# EIT_sample_circuit_with_shorter_connecto.net
KiCad netlist of a schematic drawn in EAGLE
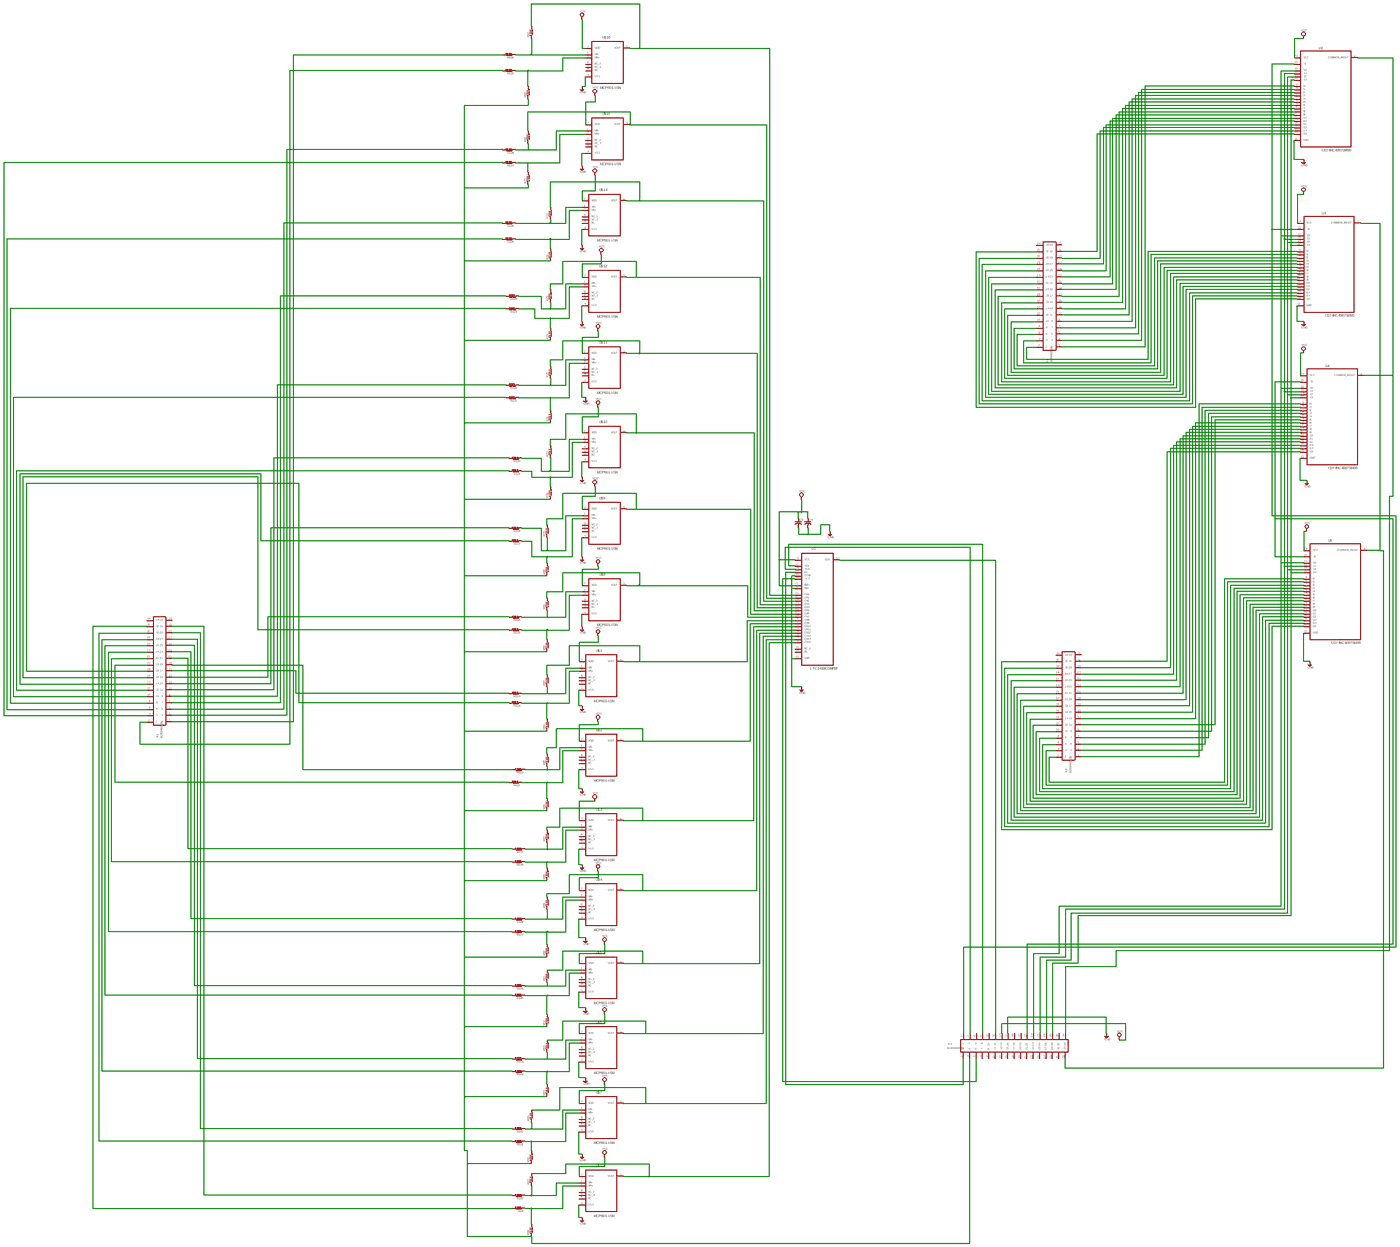
[diagram p0: schematic, sheet 1, overview]
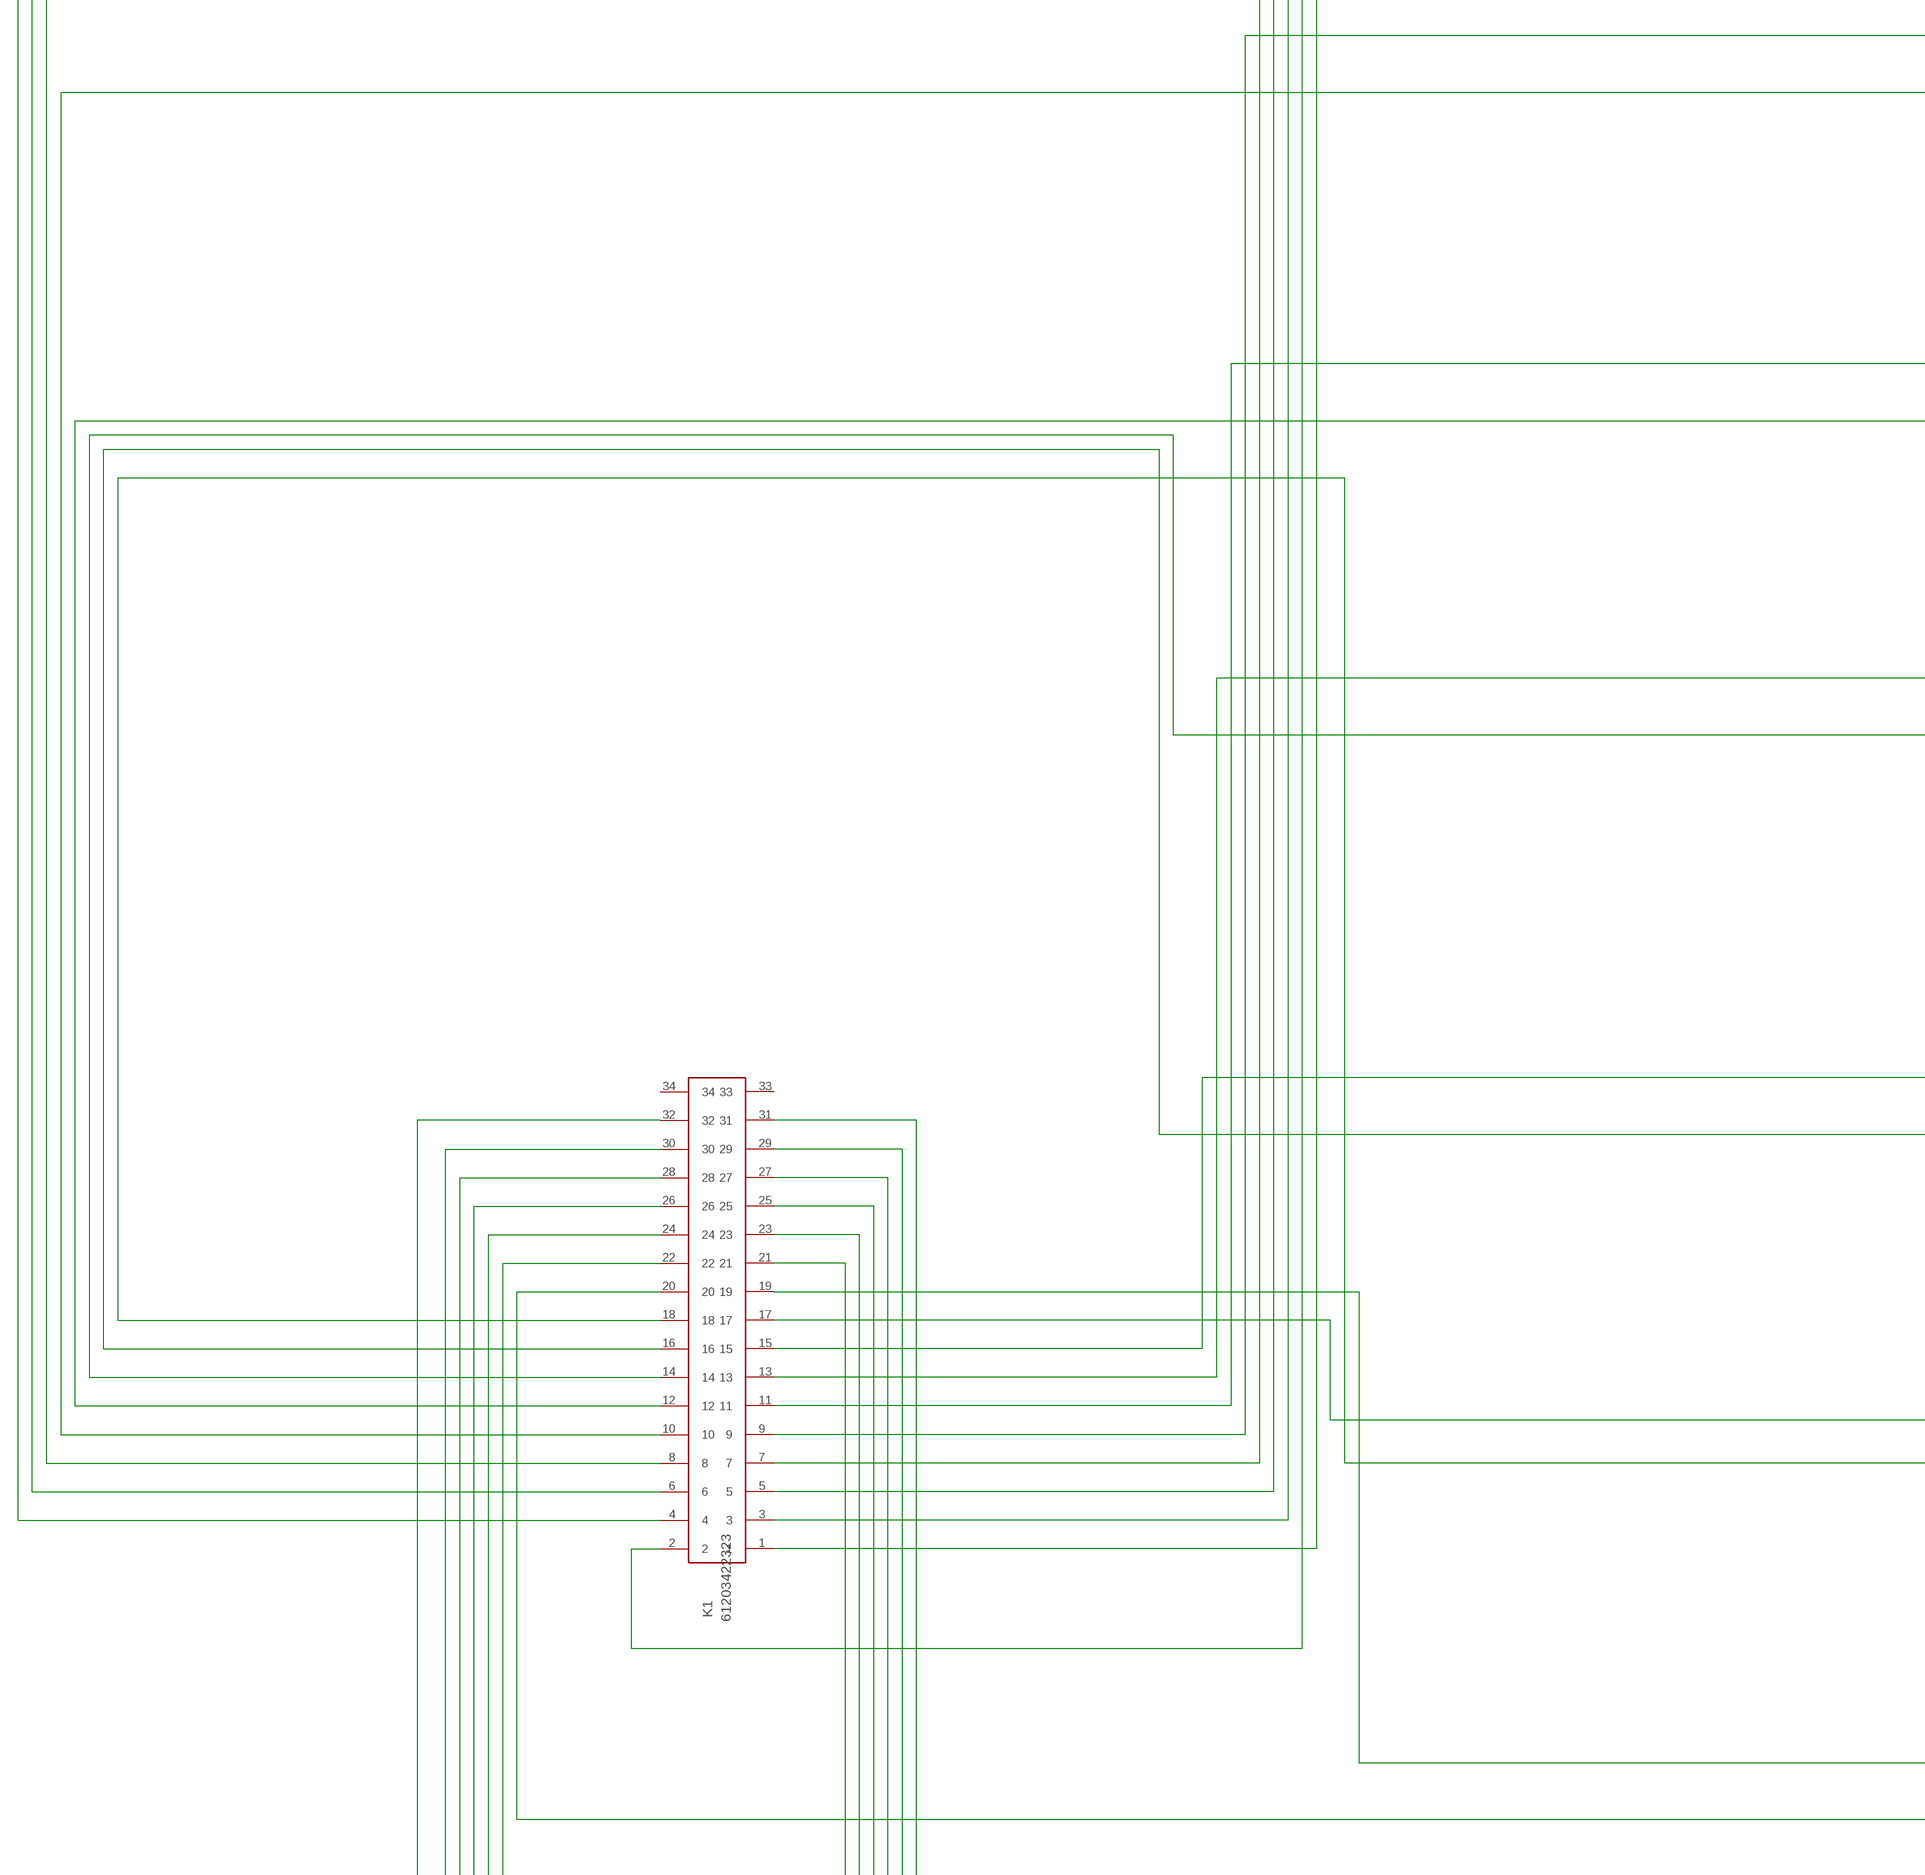
[diagram p1: schematic, sheet 1, part 1 of 7]
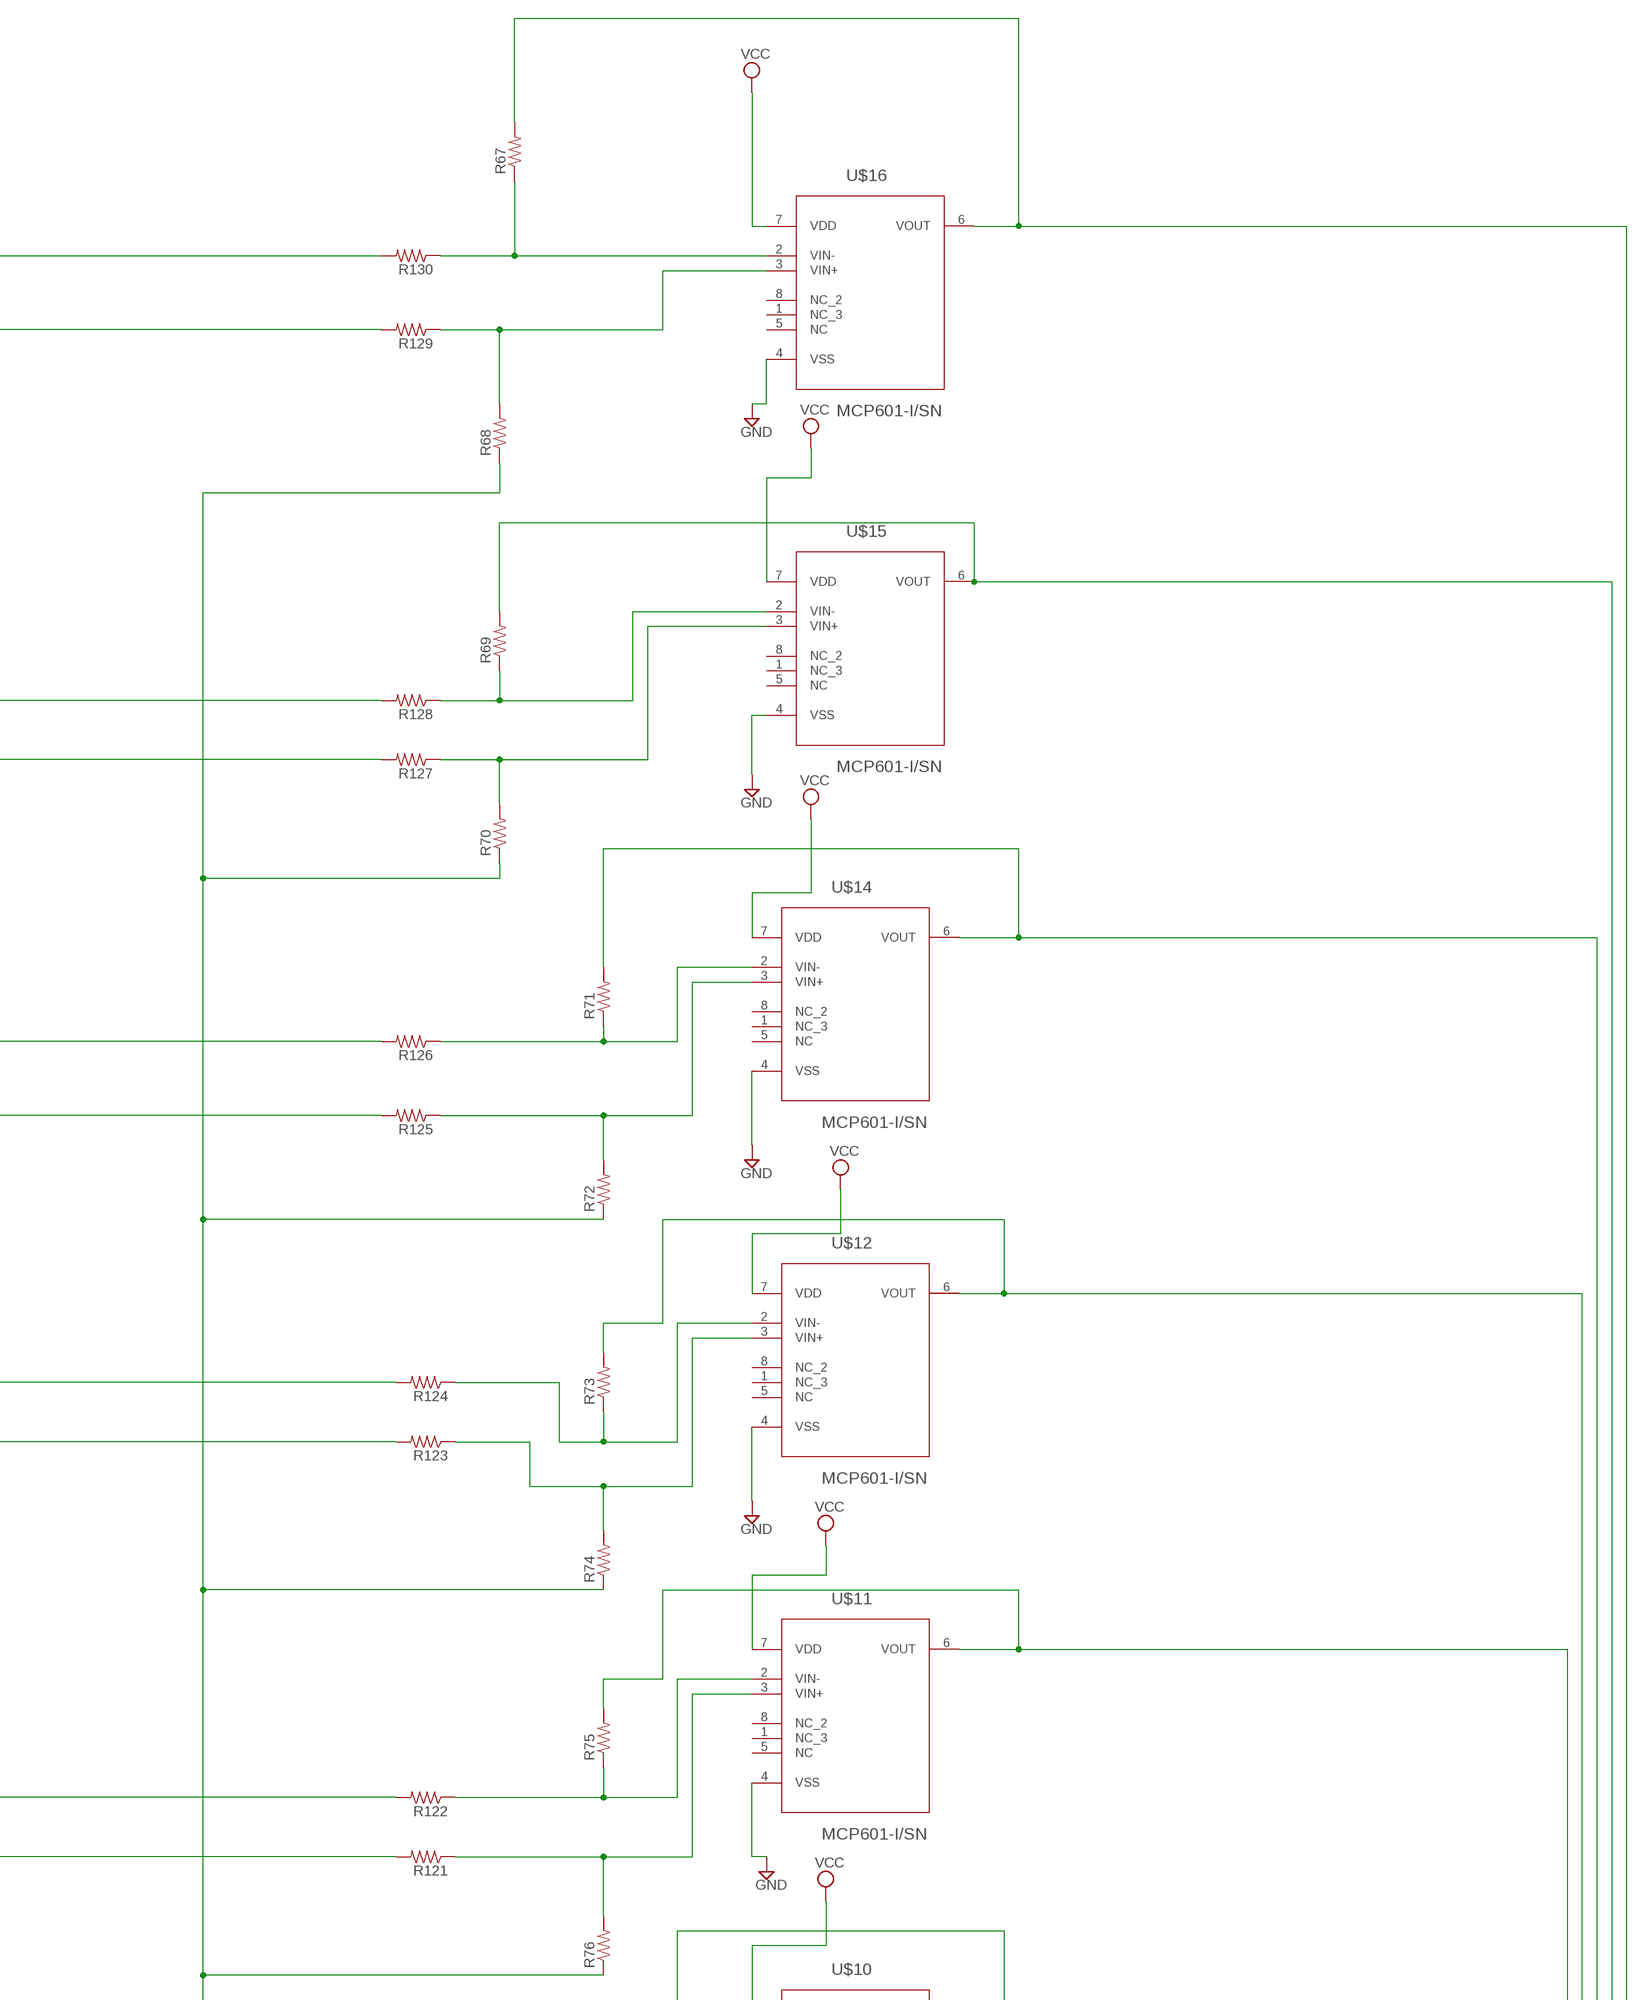
[diagram p2: schematic, sheet 1, part 2 of 7]
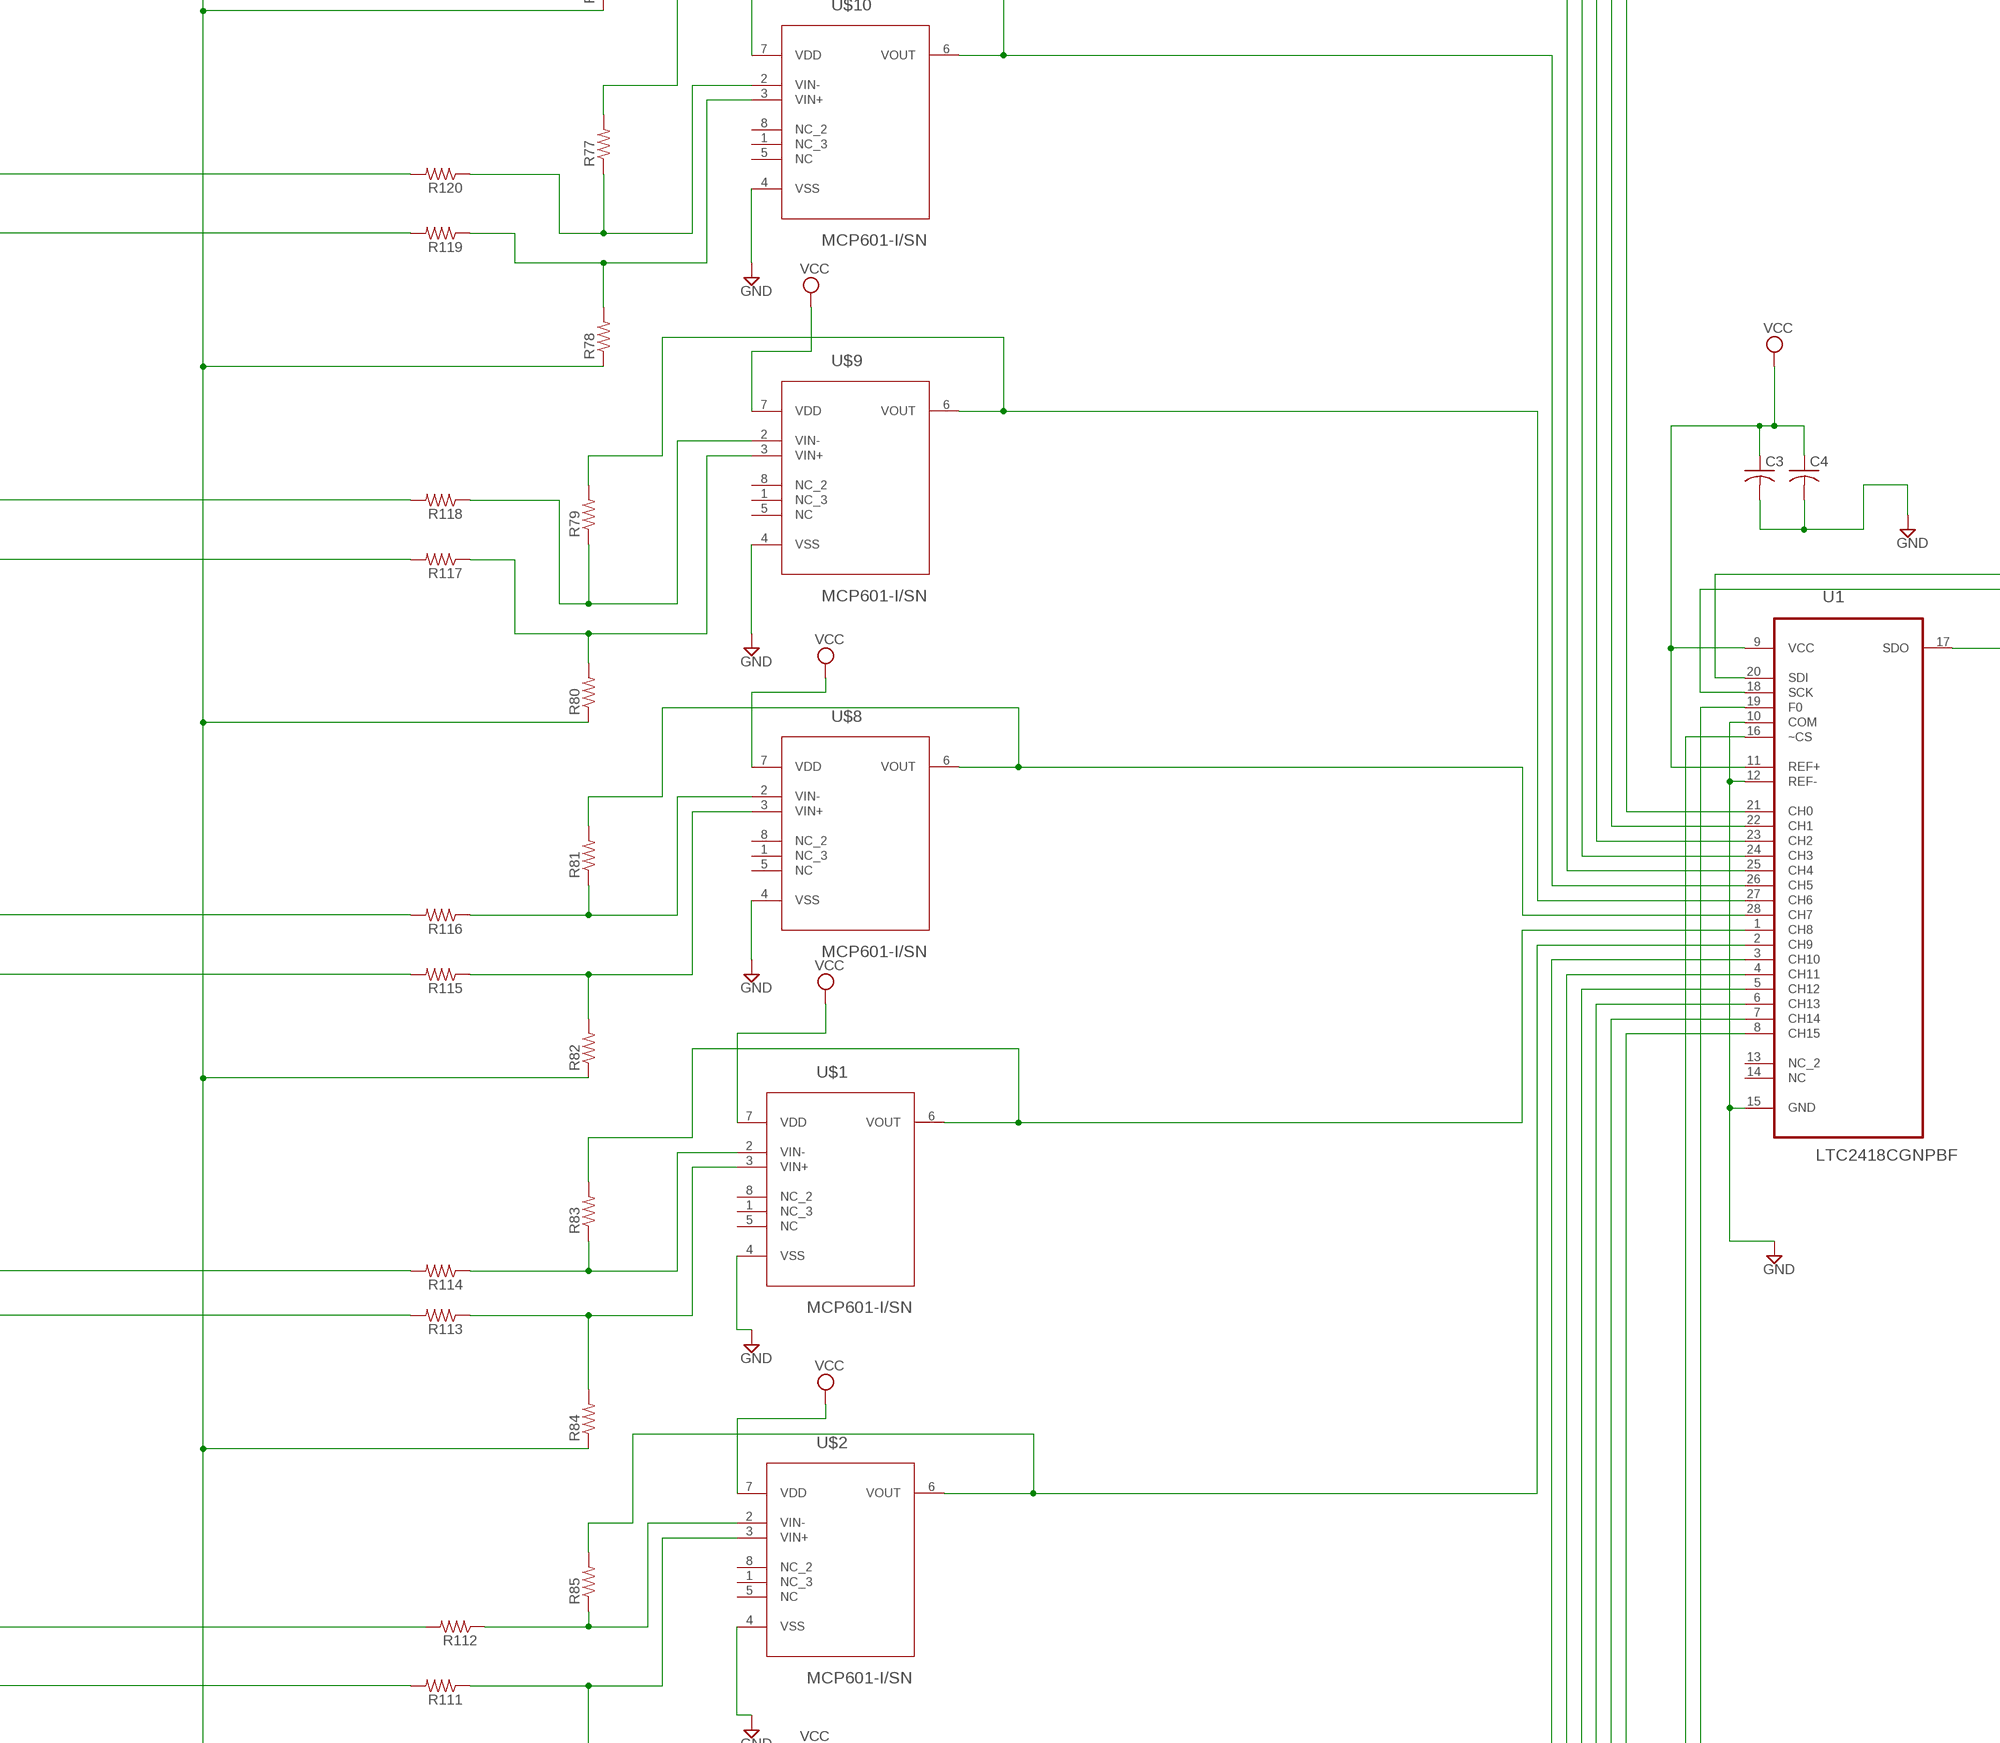
[diagram p3: schematic, sheet 1, part 3 of 7]
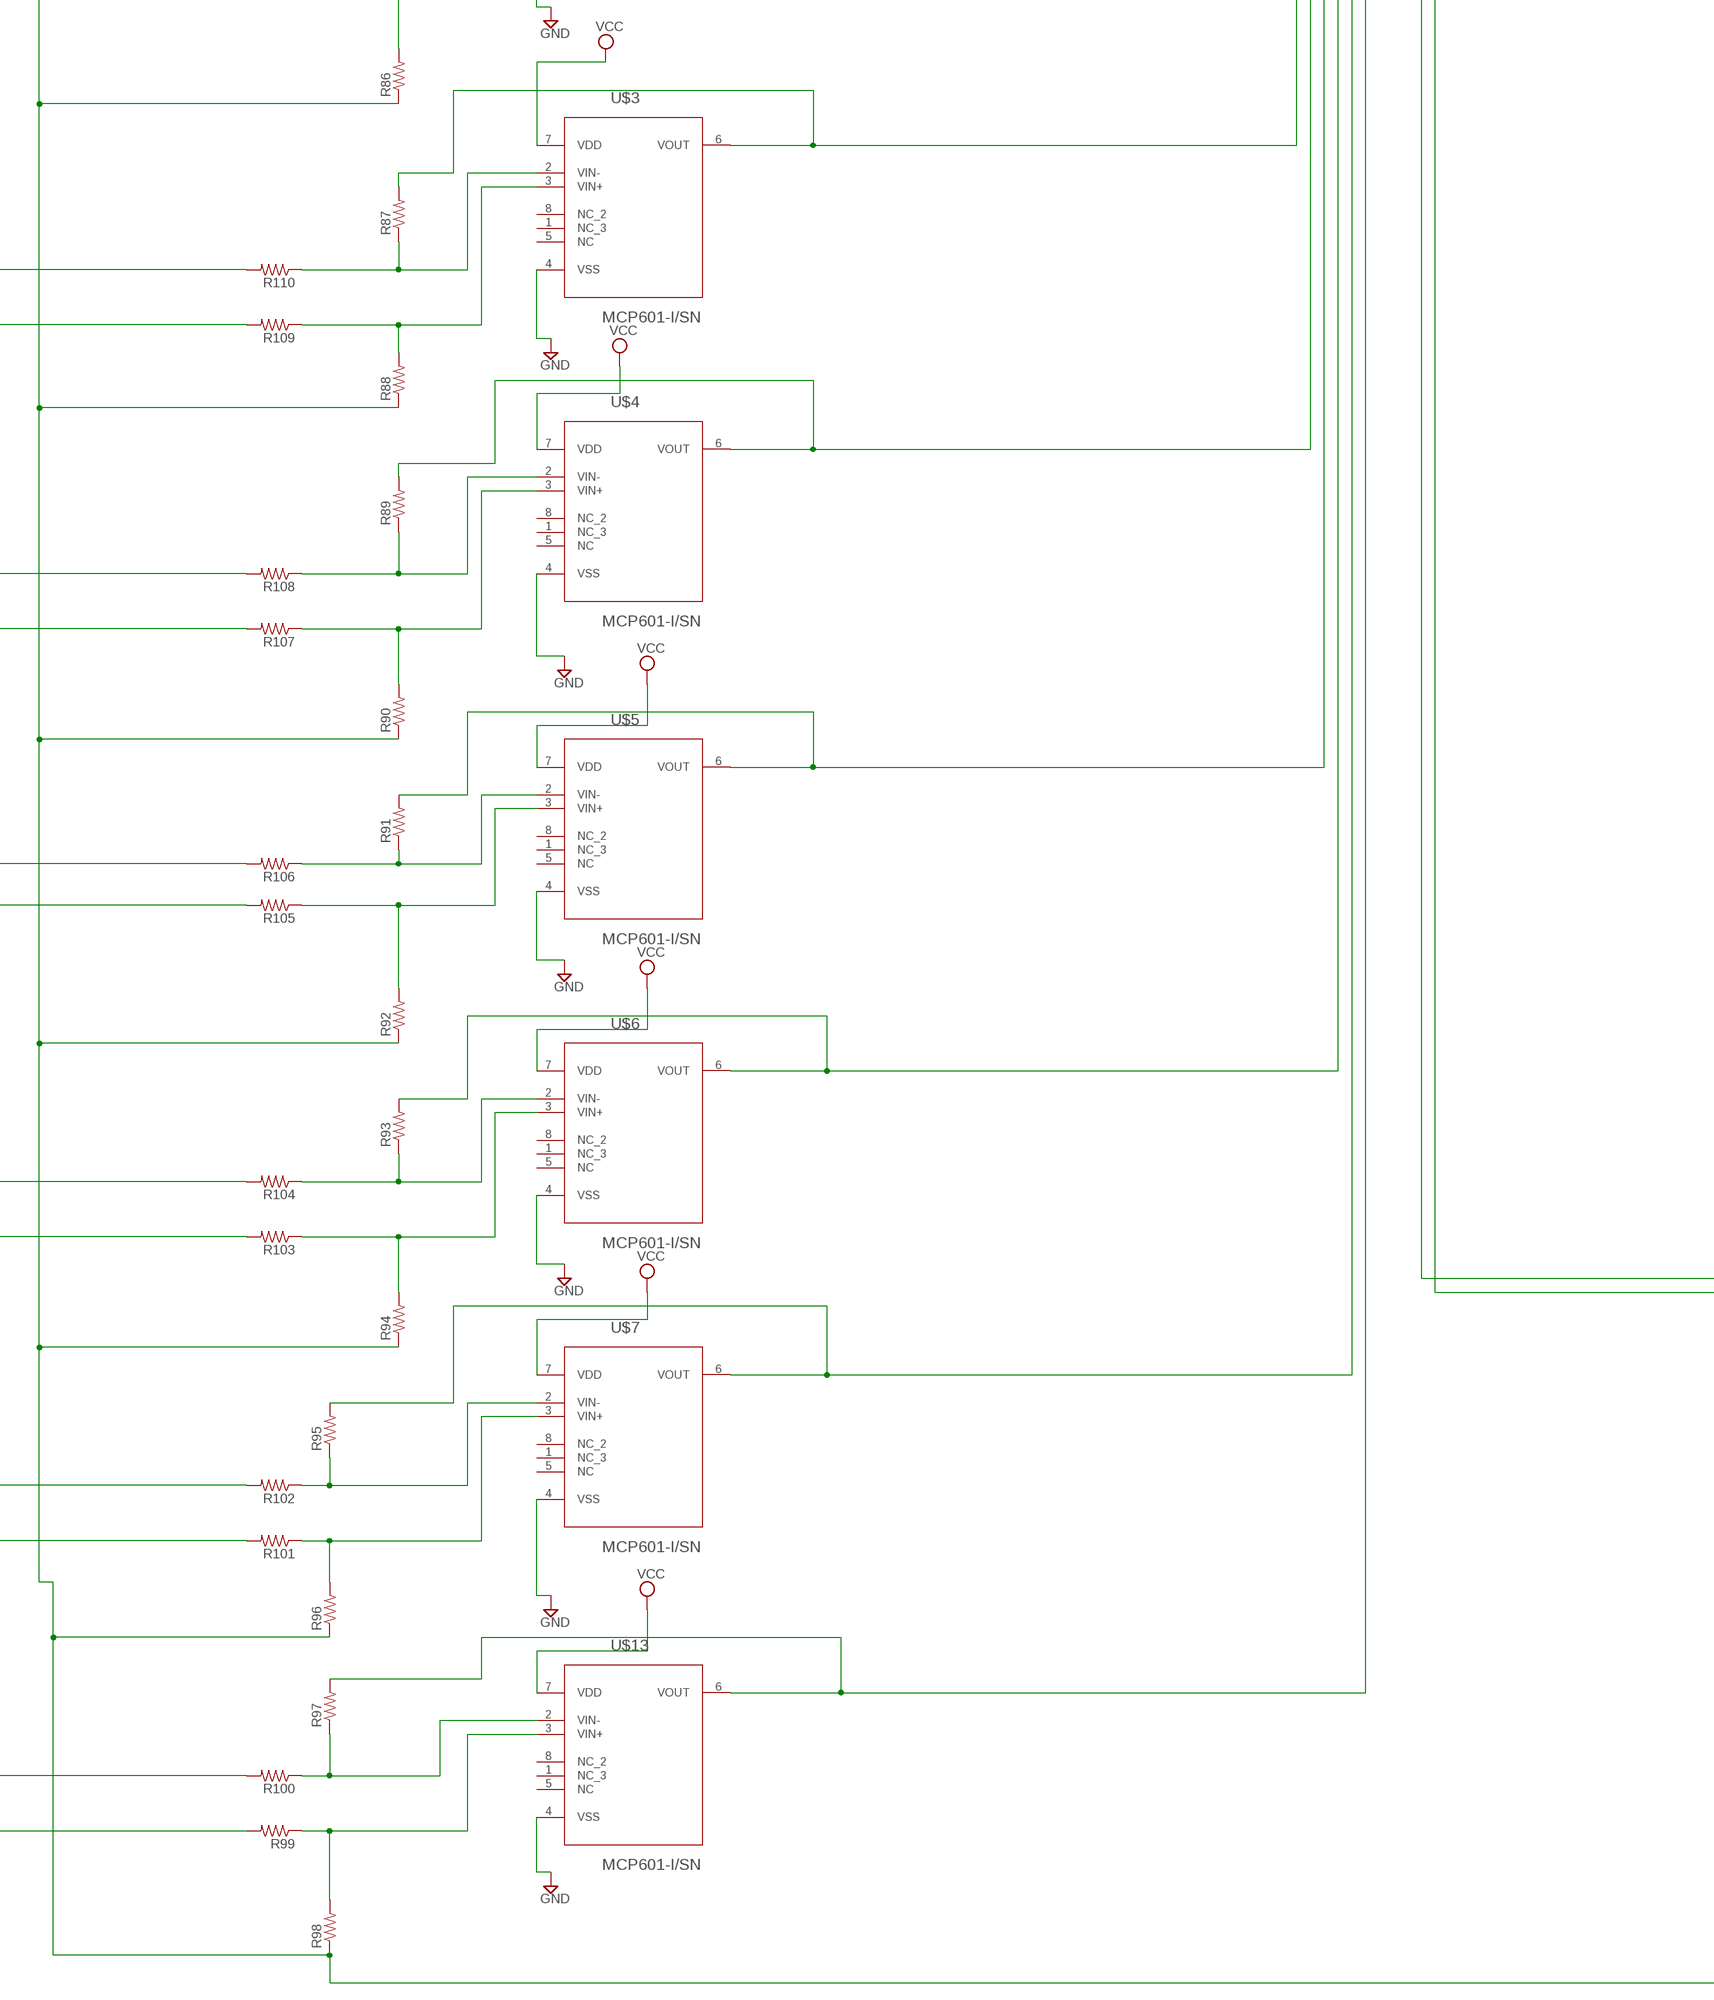
[diagram p4: schematic, sheet 1, part 4 of 7]
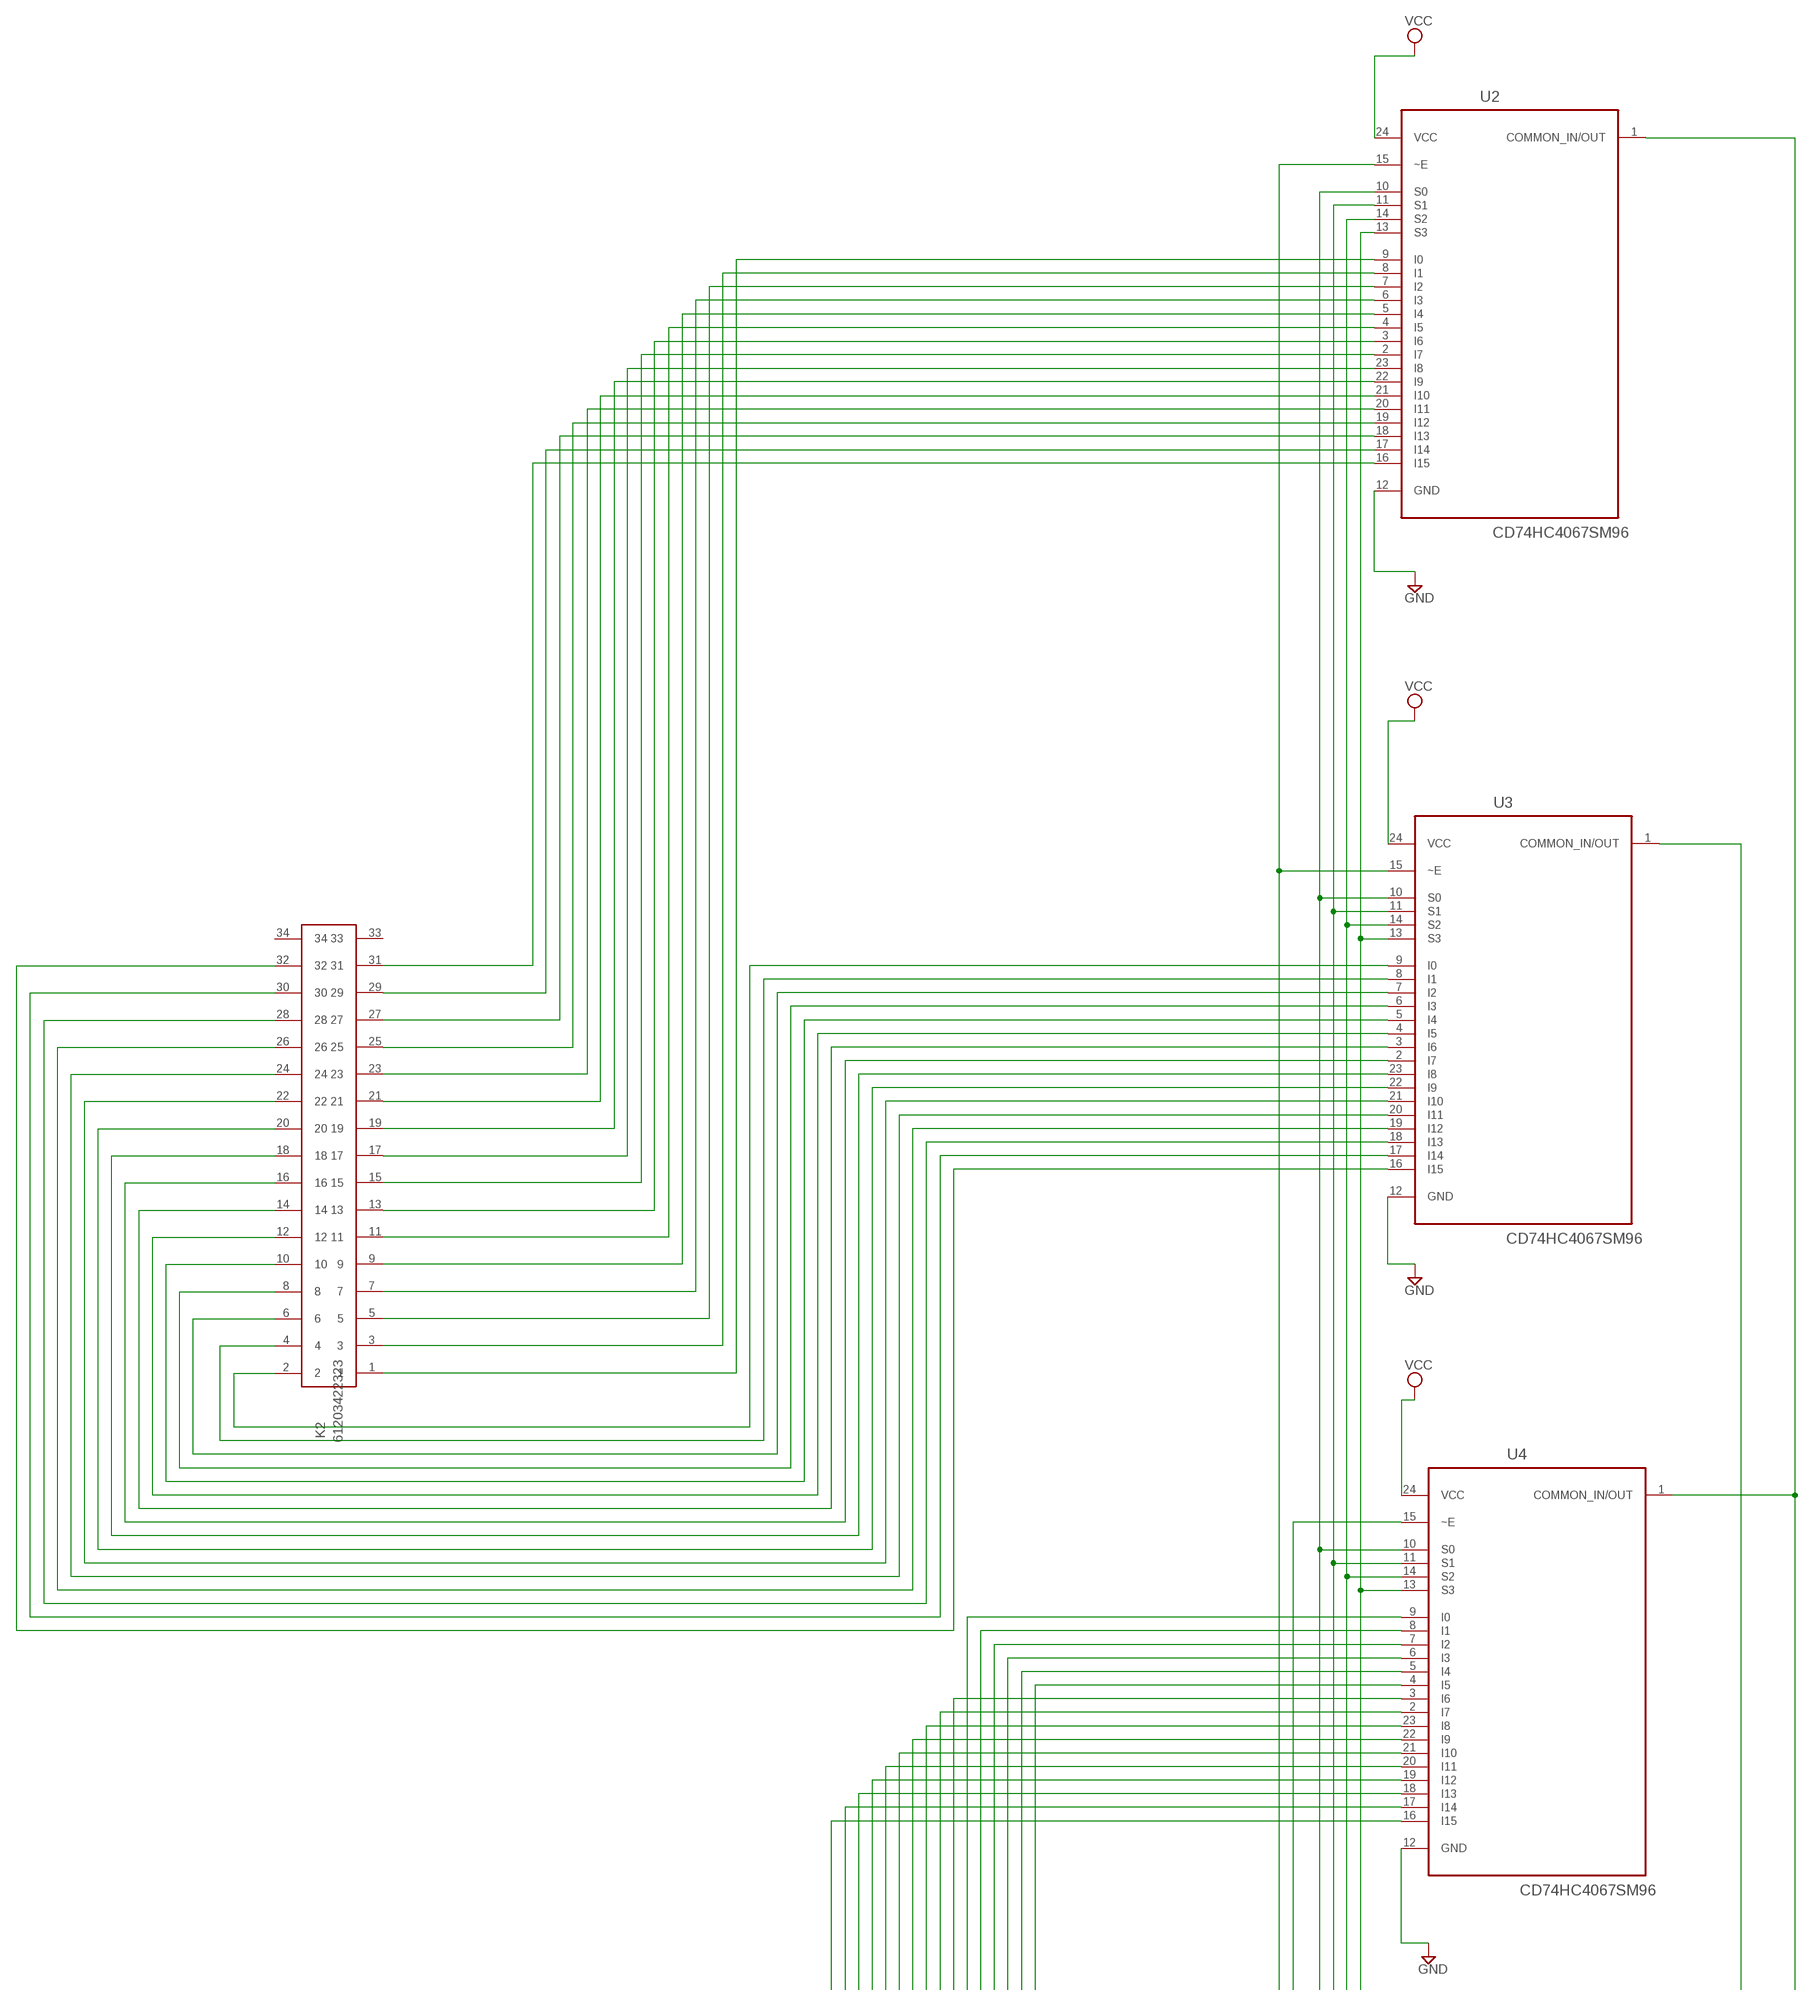
[diagram p5: schematic, sheet 1, part 5 of 7]
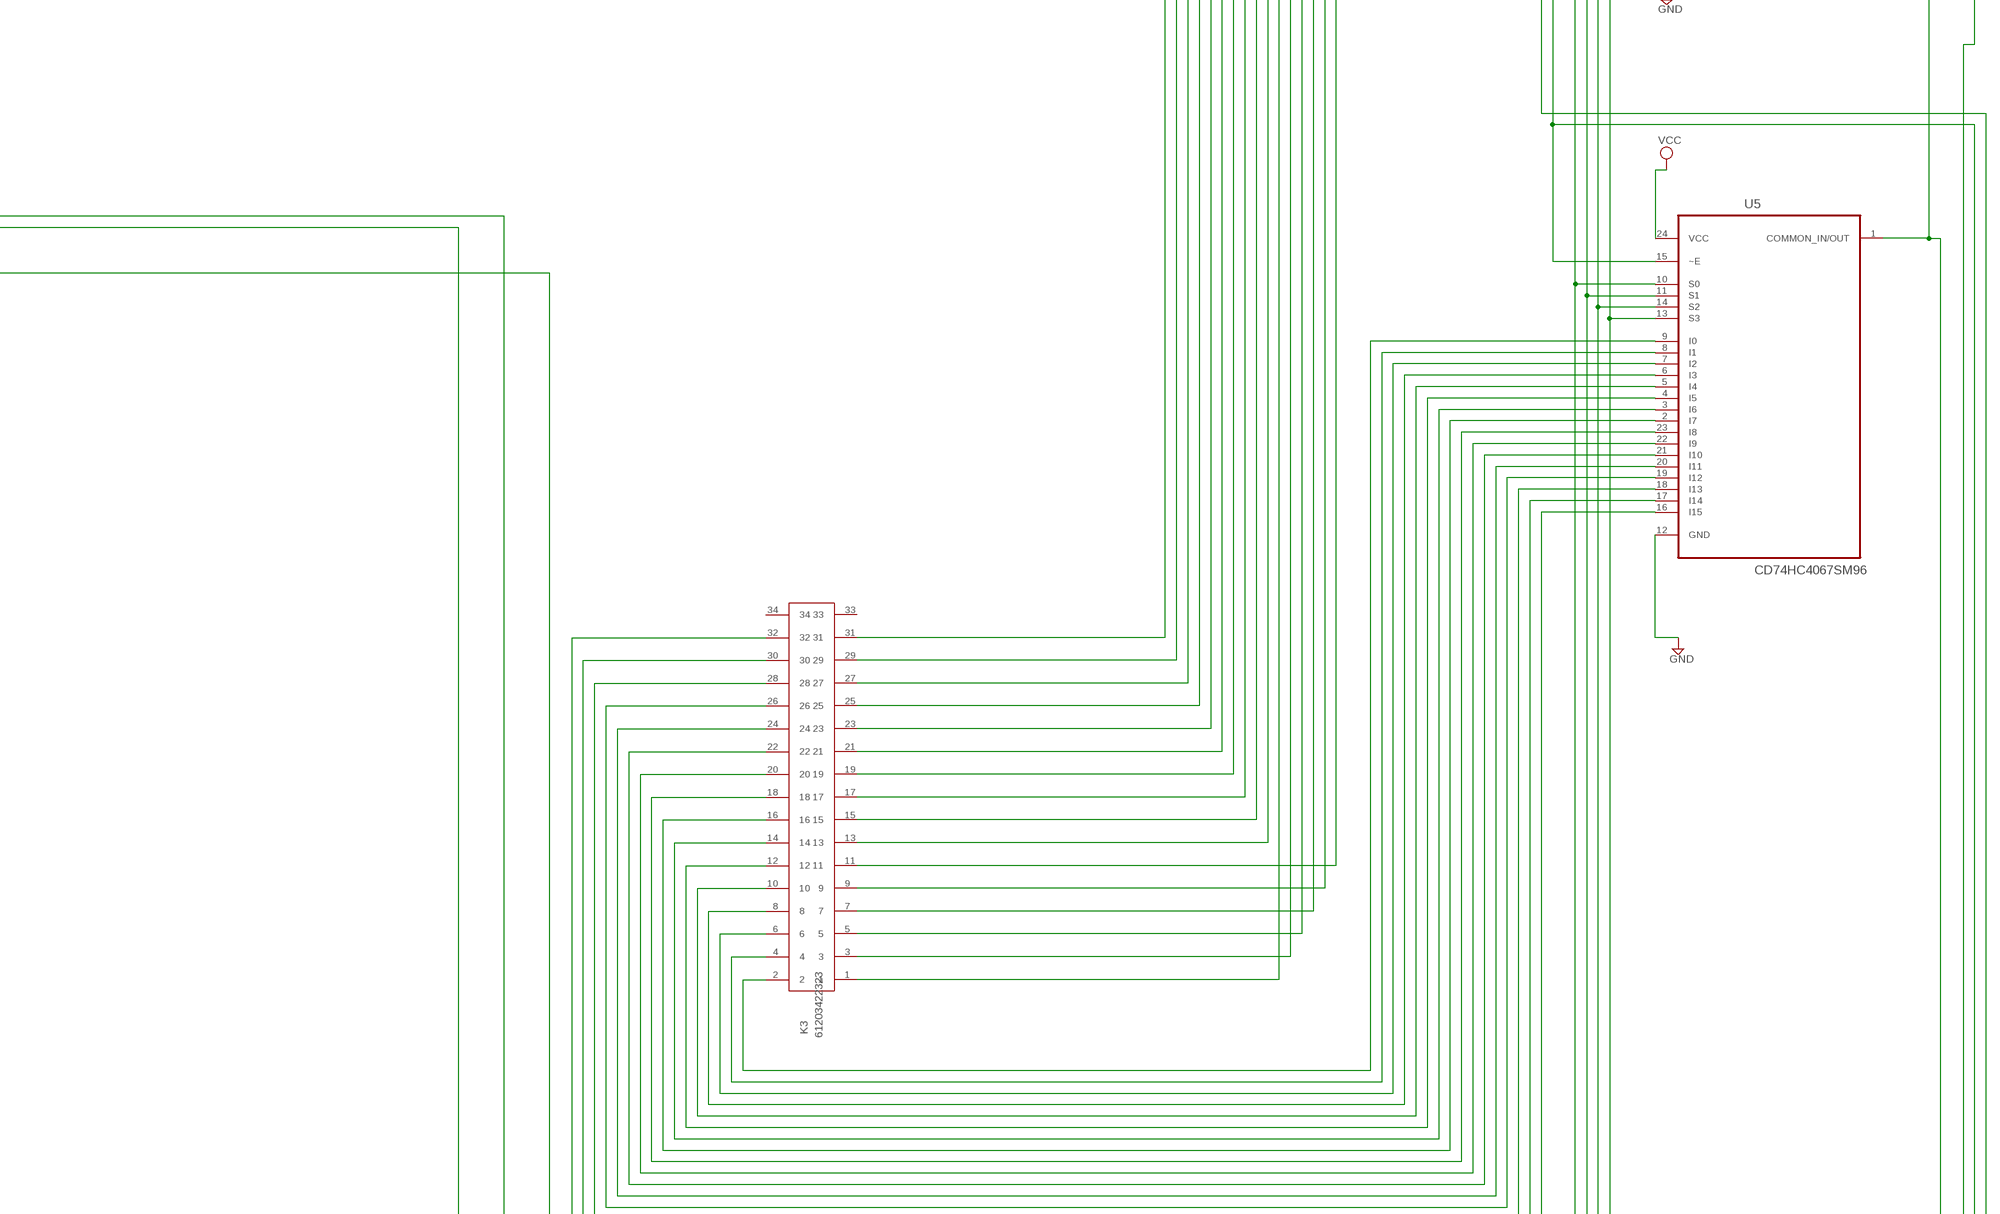
[diagram p6: schematic, sheet 1, part 6 of 7]
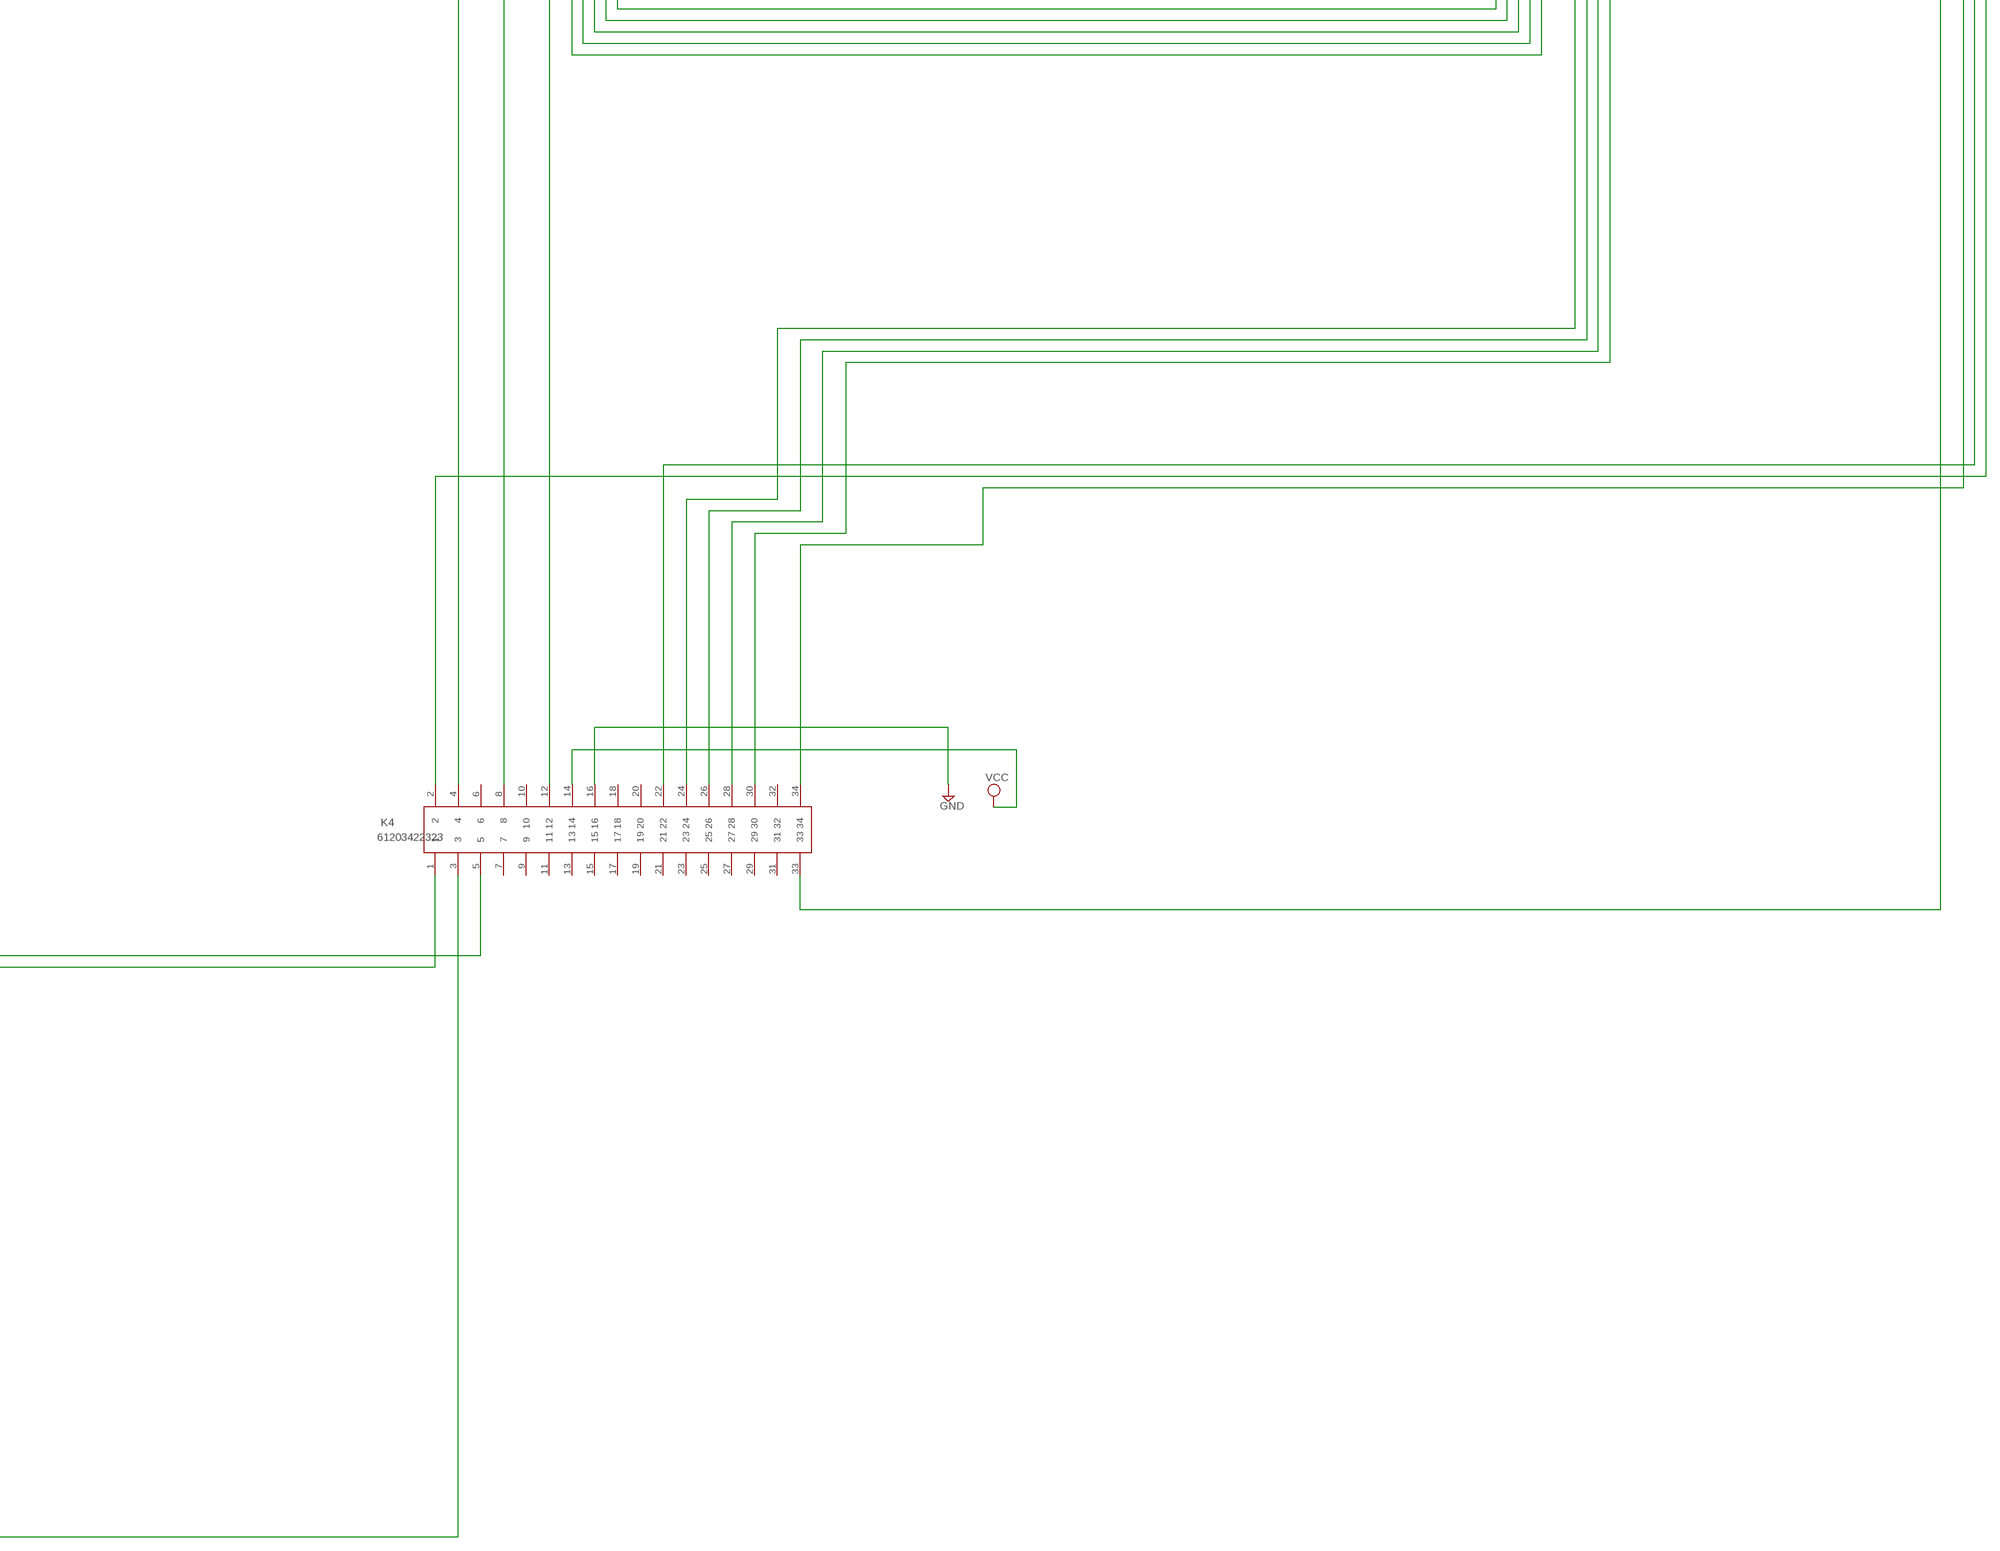
[diagram p7: schematic, sheet 1, part 7 of 7]

(export (version "E")
  (design (tool "Eeschema 10.0.6"))
  (components
    (comp (ref "C3")
      (value "C-US050-030X075")
      (footprint "eagle-import:C050-030X075")
      (libsource (lib "eagle-import") (part "C-US050-030X075"))
    )
    (comp (ref "C4")
      (value "C-US050-030X075")
      (footprint "eagle-import:C050-030X075")
      (libsource (lib "eagle-import") (part "C-US050-030X075"))
    )
    (comp (ref "K1")
      (value "61203422323")
      (footprint "eagle-import:61203422323")
      (libsource (lib "eagle-import") (part "61203422323"))
    )
    (comp (ref "K2")
      (value "61203422323")
      (footprint "eagle-import:61203422323")
      (libsource (lib "eagle-import") (part "61203422323"))
    )
    (comp (ref "K3")
      (value "61203422323")
      (footprint "eagle-import:61203422323")
      (libsource (lib "eagle-import") (part "61203422323"))
    )
    (comp (ref "K4")
      (value "61203422323")
      (footprint "eagle-import:61203422323")
      (libsource (lib "eagle-import") (part "61203422323"))
    )
    (comp (ref "R67")
      (value "R-US_0207/10")
      (footprint "eagle-import:0207_10")
      (libsource (lib "eagle-import") (part "R-US_0207/10"))
    )
    (comp (ref "R68")
      (value "R-US_0207/10")
      (footprint "eagle-import:0207_10")
      (libsource (lib "eagle-import") (part "R-US_0207/10"))
    )
    (comp (ref "R69")
      (value "R-US_0207/10")
      (footprint "eagle-import:0207_10")
      (libsource (lib "eagle-import") (part "R-US_0207/10"))
    )
    (comp (ref "R70")
      (value "R-US_0207/10")
      (footprint "eagle-import:0207_10")
      (libsource (lib "eagle-import") (part "R-US_0207/10"))
    )
    (comp (ref "R71")
      (value "R-US_0207/10")
      (footprint "eagle-import:0207_10")
      (libsource (lib "eagle-import") (part "R-US_0207/10"))
    )
    (comp (ref "R72")
      (value "R-US_0207/10")
      (footprint "eagle-import:0207_10")
      (libsource (lib "eagle-import") (part "R-US_0207/10"))
    )
    (comp (ref "R73")
      (value "R-US_0207/10")
      (footprint "eagle-import:0207_10")
      (libsource (lib "eagle-import") (part "R-US_0207/10"))
    )
    (comp (ref "R74")
      (value "R-US_0207/10")
      (footprint "eagle-import:0207_10")
      (libsource (lib "eagle-import") (part "R-US_0207/10"))
    )
    (comp (ref "R75")
      (value "R-US_0207/10")
      (footprint "eagle-import:0207_10")
      (libsource (lib "eagle-import") (part "R-US_0207/10"))
    )
    (comp (ref "R76")
      (value "R-US_0207/10")
      (footprint "eagle-import:0207_10")
      (libsource (lib "eagle-import") (part "R-US_0207/10"))
    )
    (comp (ref "R77")
      (value "R-US_0207/10")
      (footprint "eagle-import:0207_10")
      (libsource (lib "eagle-import") (part "R-US_0207/10"))
    )
    (comp (ref "R78")
      (value "R-US_0207/10")
      (footprint "eagle-import:0207_10")
      (libsource (lib "eagle-import") (part "R-US_0207/10"))
    )
    (comp (ref "R79")
      (value "R-US_0207/10")
      (footprint "eagle-import:0207_10")
      (libsource (lib "eagle-import") (part "R-US_0207/10"))
    )
    (comp (ref "R80")
      (value "R-US_0207/10")
      (footprint "eagle-import:0207_10")
      (libsource (lib "eagle-import") (part "R-US_0207/10"))
    )
    (comp (ref "R81")
      (value "R-US_0207/10")
      (footprint "eagle-import:0207_10")
      (libsource (lib "eagle-import") (part "R-US_0207/10"))
    )
    (comp (ref "R82")
      (value "R-US_0207/10")
      (footprint "eagle-import:0207_10")
      (libsource (lib "eagle-import") (part "R-US_0207/10"))
    )
    (comp (ref "R83")
      (value "R-US_0207/10")
      (footprint "eagle-import:0207_10")
      (libsource (lib "eagle-import") (part "R-US_0207/10"))
    )
    (comp (ref "R84")
      (value "R-US_0207/10")
      (footprint "eagle-import:0207_10")
      (libsource (lib "eagle-import") (part "R-US_0207/10"))
    )
    (comp (ref "R85")
      (value "R-US_0207/10")
      (footprint "eagle-import:0207_10")
      (libsource (lib "eagle-import") (part "R-US_0207/10"))
    )
    (comp (ref "R86")
      (value "R-US_0207/10")
      (footprint "eagle-import:0207_10")
      (libsource (lib "eagle-import") (part "R-US_0207/10"))
    )
    (comp (ref "R87")
      (value "R-US_0207/10")
      (footprint "eagle-import:0207_10")
      (libsource (lib "eagle-import") (part "R-US_0207/10"))
    )
    (comp (ref "R88")
      (value "R-US_0207/10")
      (footprint "eagle-import:0207_10")
      (libsource (lib "eagle-import") (part "R-US_0207/10"))
    )
    (comp (ref "R89")
      (value "R-US_0207/10")
      (footprint "eagle-import:0207_10")
      (libsource (lib "eagle-import") (part "R-US_0207/10"))
    )
    (comp (ref "R90")
      (value "R-US_0207/10")
      (footprint "eagle-import:0207_10")
      (libsource (lib "eagle-import") (part "R-US_0207/10"))
    )
    (comp (ref "R91")
      (value "R-US_0207/10")
      (footprint "eagle-import:0207_10")
      (libsource (lib "eagle-import") (part "R-US_0207/10"))
    )
    (comp (ref "R92")
      (value "R-US_0207/10")
      (footprint "eagle-import:0207_10")
      (libsource (lib "eagle-import") (part "R-US_0207/10"))
    )
    (comp (ref "R93")
      (value "R-US_0207/10")
      (footprint "eagle-import:0207_10")
      (libsource (lib "eagle-import") (part "R-US_0207/10"))
    )
    (comp (ref "R94")
      (value "R-US_0207/10")
      (footprint "eagle-import:0207_10")
      (libsource (lib "eagle-import") (part "R-US_0207/10"))
    )
    (comp (ref "R95")
      (value "R-US_0207/10")
      (footprint "eagle-import:0207_10")
      (libsource (lib "eagle-import") (part "R-US_0207/10"))
    )
    (comp (ref "R96")
      (value "R-US_0207/10")
      (footprint "eagle-import:0207_10")
      (libsource (lib "eagle-import") (part "R-US_0207/10"))
    )
    (comp (ref "R97")
      (value "R-US_0207/10")
      (footprint "eagle-import:0207_10")
      (libsource (lib "eagle-import") (part "R-US_0207/10"))
    )
    (comp (ref "R98")
      (value "R-US_0207/10")
      (footprint "eagle-import:0207_10")
      (libsource (lib "eagle-import") (part "R-US_0207/10"))
    )
    (comp (ref "R99")
      (value "R-US_0207/7")
      (footprint "eagle-import:0207_7")
      (libsource (lib "eagle-import") (part "R-US_0207/7"))
    )
    (comp (ref "R100")
      (value "R-US_0207/7")
      (footprint "eagle-import:0207_7")
      (libsource (lib "eagle-import") (part "R-US_0207/7"))
    )
    (comp (ref "R101")
      (value "R-US_0207/7")
      (footprint "eagle-import:0207_7")
      (libsource (lib "eagle-import") (part "R-US_0207/7"))
    )
    (comp (ref "R102")
      (value "R-US_0207/7")
      (footprint "eagle-import:0207_7")
      (libsource (lib "eagle-import") (part "R-US_0207/7"))
    )
    (comp (ref "R103")
      (value "R-US_0207/7")
      (footprint "eagle-import:0207_7")
      (libsource (lib "eagle-import") (part "R-US_0207/7"))
    )
    (comp (ref "R104")
      (value "R-US_0207/7")
      (footprint "eagle-import:0207_7")
      (libsource (lib "eagle-import") (part "R-US_0207/7"))
    )
    (comp (ref "R105")
      (value "R-US_0207/7")
      (footprint "eagle-import:0207_7")
      (libsource (lib "eagle-import") (part "R-US_0207/7"))
    )
    (comp (ref "R106")
      (value "R-US_0207/7")
      (footprint "eagle-import:0207_7")
      (libsource (lib "eagle-import") (part "R-US_0207/7"))
    )
    (comp (ref "R107")
      (value "R-US_0207/7")
      (footprint "eagle-import:0207_7")
      (libsource (lib "eagle-import") (part "R-US_0207/7"))
    )
    (comp (ref "R108")
      (value "R-US_0207/7")
      (footprint "eagle-import:0207_7")
      (libsource (lib "eagle-import") (part "R-US_0207/7"))
    )
    (comp (ref "R109")
      (value "R-US_0207/7")
      (footprint "eagle-import:0207_7")
      (libsource (lib "eagle-import") (part "R-US_0207/7"))
    )
    (comp (ref "R110")
      (value "R-US_0207/7")
      (footprint "eagle-import:0207_7")
      (libsource (lib "eagle-import") (part "R-US_0207/7"))
    )
    (comp (ref "R111")
      (value "R-US_0207/7")
      (footprint "eagle-import:0207_7")
      (libsource (lib "eagle-import") (part "R-US_0207/7"))
    )
    (comp (ref "R112")
      (value "R-US_0207/7")
      (footprint "eagle-import:0207_7")
      (libsource (lib "eagle-import") (part "R-US_0207/7"))
    )
    (comp (ref "R113")
      (value "R-US_0207/7")
      (footprint "eagle-import:0207_7")
      (libsource (lib "eagle-import") (part "R-US_0207/7"))
    )
    (comp (ref "R114")
      (value "R-US_0207/7")
      (footprint "eagle-import:0207_7")
      (libsource (lib "eagle-import") (part "R-US_0207/7"))
    )
    (comp (ref "R115")
      (value "R-US_0207/7")
      (footprint "eagle-import:0207_7")
      (libsource (lib "eagle-import") (part "R-US_0207/7"))
    )
    (comp (ref "R116")
      (value "R-US_0207/7")
      (footprint "eagle-import:0207_7")
      (libsource (lib "eagle-import") (part "R-US_0207/7"))
    )
    (comp (ref "R117")
      (value "R-US_0207/7")
      (footprint "eagle-import:0207_7")
      (libsource (lib "eagle-import") (part "R-US_0207/7"))
    )
    (comp (ref "R118")
      (value "R-US_0207/7")
      (footprint "eagle-import:0207_7")
      (libsource (lib "eagle-import") (part "R-US_0207/7"))
    )
    (comp (ref "R119")
      (value "R-US_0207/7")
      (footprint "eagle-import:0207_7")
      (libsource (lib "eagle-import") (part "R-US_0207/7"))
    )
    (comp (ref "R120")
      (value "R-US_0207/7")
      (footprint "eagle-import:0207_7")
      (libsource (lib "eagle-import") (part "R-US_0207/7"))
    )
    (comp (ref "R121")
      (value "R-US_0207/7")
      (footprint "eagle-import:0207_7")
      (libsource (lib "eagle-import") (part "R-US_0207/7"))
    )
    (comp (ref "R122")
      (value "R-US_0207/7")
      (footprint "eagle-import:0207_7")
      (libsource (lib "eagle-import") (part "R-US_0207/7"))
    )
    (comp (ref "R123")
      (value "R-US_0207/7")
      (footprint "eagle-import:0207_7")
      (libsource (lib "eagle-import") (part "R-US_0207/7"))
    )
    (comp (ref "R124")
      (value "R-US_0207/7")
      (footprint "eagle-import:0207_7")
      (libsource (lib "eagle-import") (part "R-US_0207/7"))
    )
    (comp (ref "R125")
      (value "R-US_0207/7")
      (footprint "eagle-import:0207_7")
      (libsource (lib "eagle-import") (part "R-US_0207/7"))
    )
    (comp (ref "R126")
      (value "R-US_0207/7")
      (footprint "eagle-import:0207_7")
      (libsource (lib "eagle-import") (part "R-US_0207/7"))
    )
    (comp (ref "R127")
      (value "R-US_0207/7")
      (footprint "eagle-import:0207_7")
      (libsource (lib "eagle-import") (part "R-US_0207/7"))
    )
    (comp (ref "R128")
      (value "R-US_0207/7")
      (footprint "eagle-import:0207_7")
      (libsource (lib "eagle-import") (part "R-US_0207/7"))
    )
    (comp (ref "R129")
      (value "R-US_0207/7")
      (footprint "eagle-import:0207_7")
      (libsource (lib "eagle-import") (part "R-US_0207/7"))
    )
    (comp (ref "R130")
      (value "R-US_0207/7")
      (footprint "eagle-import:0207_7")
      (libsource (lib "eagle-import") (part "R-US_0207/7"))
    )
    (comp (ref "U$1")
      (value "MCP601-I/SN")
      (footprint "eagle-import:SOIC127P600X175-8N")
      (libsource (lib "eagle-import") (part "MCP601-I/SN"))
    )
    (comp (ref "U$2")
      (value "MCP601-I/SN")
      (footprint "eagle-import:SOIC127P600X175-8N")
      (libsource (lib "eagle-import") (part "MCP601-I/SN"))
    )
    (comp (ref "U$3")
      (value "MCP601-I/SN")
      (footprint "eagle-import:SOIC127P600X175-8N")
      (libsource (lib "eagle-import") (part "MCP601-I/SN"))
    )
    (comp (ref "U$4")
      (value "MCP601-I/SN")
      (footprint "eagle-import:SOIC127P600X175-8N")
      (libsource (lib "eagle-import") (part "MCP601-I/SN"))
    )
    (comp (ref "U$5")
      (value "MCP601-I/SN")
      (footprint "eagle-import:SOIC127P600X175-8N")
      (libsource (lib "eagle-import") (part "MCP601-I/SN"))
    )
    (comp (ref "U$6")
      (value "MCP601-I/SN")
      (footprint "eagle-import:SOIC127P600X175-8N")
      (libsource (lib "eagle-import") (part "MCP601-I/SN"))
    )
    (comp (ref "U$7")
      (value "MCP601-I/SN")
      (footprint "eagle-import:SOIC127P600X175-8N")
      (libsource (lib "eagle-import") (part "MCP601-I/SN"))
    )
    (comp (ref "U$8")
      (value "MCP601-I/SN")
      (footprint "eagle-import:SOIC127P600X175-8N")
      (libsource (lib "eagle-import") (part "MCP601-I/SN"))
    )
    (comp (ref "U$9")
      (value "MCP601-I/SN")
      (footprint "eagle-import:SOIC127P600X175-8N")
      (libsource (lib "eagle-import") (part "MCP601-I/SN"))
    )
    (comp (ref "U$10")
      (value "MCP601-I/SN")
      (footprint "eagle-import:SOIC127P600X175-8N")
      (libsource (lib "eagle-import") (part "MCP601-I/SN"))
    )
    (comp (ref "U$11")
      (value "MCP601-I/SN")
      (footprint "eagle-import:SOIC127P600X175-8N")
      (libsource (lib "eagle-import") (part "MCP601-I/SN"))
    )
    (comp (ref "U$12")
      (value "MCP601-I/SN")
      (footprint "eagle-import:SOIC127P600X175-8N")
      (libsource (lib "eagle-import") (part "MCP601-I/SN"))
    )
    (comp (ref "U$13")
      (value "MCP601-I/SN")
      (footprint "eagle-import:SOIC127P600X175-8N")
      (libsource (lib "eagle-import") (part "MCP601-I/SN"))
    )
    (comp (ref "U$14")
      (value "MCP601-I/SN")
      (footprint "eagle-import:SOIC127P600X175-8N")
      (libsource (lib "eagle-import") (part "MCP601-I/SN"))
    )
    (comp (ref "U$15")
      (value "MCP601-I/SN")
      (footprint "eagle-import:SOIC127P600X175-8N")
      (libsource (lib "eagle-import") (part "MCP601-I/SN"))
    )
    (comp (ref "U$16")
      (value "MCP601-I/SN")
      (footprint "eagle-import:SOIC127P600X175-8N")
      (libsource (lib "eagle-import") (part "MCP601-I/SN"))
    )
    (comp (ref "U1")
      (value "LTC2418CGNPBF")
      (footprint "eagle-import:SOP63P600X175-28N")
      (fields (field (name "MPN") "LTC2418CGN#PBF"))
      (libsource (lib "eagle-import") (part "LTC2418CGNPBF"))
    )
    (comp (ref "U2")
      (value "CD74HC4067SM96")
      (footprint "eagle-import:SOP65P780X200-24N")
      (libsource (lib "eagle-import") (part "CD74HC4067SM96"))
    )
    (comp (ref "U3")
      (value "CD74HC4067SM96")
      (footprint "eagle-import:SOP65P780X200-24N")
      (libsource (lib "eagle-import") (part "CD74HC4067SM96"))
    )
    (comp (ref "U4")
      (value "CD74HC4067SM96")
      (footprint "eagle-import:SOP65P780X200-24N")
      (libsource (lib "eagle-import") (part "CD74HC4067SM96"))
    )
    (comp (ref "U5")
      (value "CD74HC4067SM96")
      (footprint "eagle-import:SOP65P780X200-24N")
      (libsource (lib "eagle-import") (part "CD74HC4067SM96"))
    )
  )
  (nets
    (net (code "1") (name "GND") (class "Default")
      (node (ref "C3") (pin "2") (pinfunction "2_2") (pintype "passive"))
      (node (ref "C4") (pin "2") (pinfunction "2_2") (pintype "passive"))
      (node (ref "K4") (pin "16") (pinfunction "16_16") (pintype "passive"))
      (node (ref "U$1") (pin "4") (pinfunction "VSS_4") (pintype "power_in"))
      (node (ref "U$10") (pin "4") (pinfunction "VSS_4") (pintype "power_in"))
      (node (ref "U$11") (pin "4") (pinfunction "VSS_4") (pintype "power_in"))
      (node (ref "U$12") (pin "4") (pinfunction "VSS_4") (pintype "power_in"))
      (node (ref "U$13") (pin "4") (pinfunction "VSS_4") (pintype "power_in"))
      (node (ref "U$14") (pin "4") (pinfunction "VSS_4") (pintype "power_in"))
      (node (ref "U$15") (pin "4") (pinfunction "VSS_4") (pintype "power_in"))
      (node (ref "U$16") (pin "4") (pinfunction "VSS_4") (pintype "power_in"))
      (node (ref "U$2") (pin "4") (pinfunction "VSS_4") (pintype "power_in"))
      (node (ref "U$3") (pin "4") (pinfunction "VSS_4") (pintype "power_in"))
      (node (ref "U$4") (pin "4") (pinfunction "VSS_4") (pintype "power_in"))
      (node (ref "U$5") (pin "4") (pinfunction "VSS_4") (pintype "power_in"))
      (node (ref "U$6") (pin "4") (pinfunction "VSS_4") (pintype "power_in"))
      (node (ref "U$7") (pin "4") (pinfunction "VSS_4") (pintype "power_in"))
      (node (ref "U$8") (pin "4") (pinfunction "VSS_4") (pintype "power_in"))
      (node (ref "U$9") (pin "4") (pinfunction "VSS_4") (pintype "power_in"))
      (node (ref "U1") (pin "10") (pinfunction "COM_10") (pintype "input"))
      (node (ref "U1") (pin "12") (pinfunction "REF-_12") (pintype "input"))
      (node (ref "U1") (pin "15") (pinfunction "GND_15") (pintype "passive"))
      (node (ref "U2") (pin "12") (pinfunction "GND_12") (pintype "passive"))
      (node (ref "U3") (pin "12") (pinfunction "GND_12") (pintype "passive"))
      (node (ref "U4") (pin "12") (pinfunction "GND_12") (pintype "passive"))
      (node (ref "U5") (pin "12") (pinfunction "GND_12") (pintype "passive"))
    )
    (net (code "2") (name "Net-(K1-Pad1)") (class "Default")
      (node (ref "K1") (pin "1") (pinfunction "1_1") (pintype "passive"))
      (node (ref "R130") (pin "2") (pinfunction "2_2") (pintype "passive"))
    )
    (net (code "3") (name "Net-(K1-Pad2)") (class "Default")
      (node (ref "K1") (pin "2") (pinfunction "2_2") (pintype "passive"))
      (node (ref "R129") (pin "2") (pinfunction "2_2") (pintype "passive"))
    )
    (net (code "4") (name "Net-(K1-Pad3)") (class "Default")
      (node (ref "K1") (pin "3") (pinfunction "3_3") (pintype "passive"))
      (node (ref "R128") (pin "2") (pinfunction "2_2") (pintype "passive"))
    )
    (net (code "5") (name "Net-(K1-Pad4)") (class "Default")
      (node (ref "K1") (pin "4") (pinfunction "4_4") (pintype "passive"))
      (node (ref "R127") (pin "2") (pinfunction "2_2") (pintype "passive"))
    )
    (net (code "6") (name "Net-(K1-Pad5)") (class "Default")
      (node (ref "K1") (pin "5") (pinfunction "5_5") (pintype "passive"))
      (node (ref "R126") (pin "2") (pinfunction "2_2") (pintype "passive"))
    )
    (net (code "7") (name "Net-(K1-Pad6)") (class "Default")
      (node (ref "K1") (pin "6") (pinfunction "6_6") (pintype "passive"))
      (node (ref "R125") (pin "2") (pinfunction "2_2") (pintype "passive"))
    )
    (net (code "8") (name "Net-(K1-Pad7)") (class "Default")
      (node (ref "K1") (pin "7") (pinfunction "7_7") (pintype "passive"))
      (node (ref "R124") (pin "2") (pinfunction "2_2") (pintype "passive"))
    )
    (net (code "9") (name "Net-(K1-Pad8)") (class "Default")
      (node (ref "K1") (pin "8") (pinfunction "8_8") (pintype "passive"))
      (node (ref "R123") (pin "2") (pinfunction "2_2") (pintype "passive"))
    )
    (net (code "10") (name "Net-(K1-Pad9)") (class "Default")
      (node (ref "K1") (pin "9") (pinfunction "9_9") (pintype "passive"))
      (node (ref "R122") (pin "2") (pinfunction "2_2") (pintype "passive"))
    )
    (net (code "11") (name "Net-(K1-Pad10)") (class "Default")
      (node (ref "K1") (pin "10") (pinfunction "10_10") (pintype "passive"))
      (node (ref "R121") (pin "2") (pinfunction "2_2") (pintype "passive"))
    )
    (net (code "12") (name "Net-(K1-Pad11)") (class "Default")
      (node (ref "K1") (pin "11") (pinfunction "11_11") (pintype "passive"))
      (node (ref "R120") (pin "2") (pinfunction "2_2") (pintype "passive"))
    )
    (net (code "13") (name "Net-(K1-Pad12)") (class "Default")
      (node (ref "K1") (pin "12") (pinfunction "12_12") (pintype "passive"))
      (node (ref "R119") (pin "2") (pinfunction "2_2") (pintype "passive"))
    )
    (net (code "14") (name "Net-(K1-Pad13)") (class "Default")
      (node (ref "K1") (pin "13") (pinfunction "13_13") (pintype "passive"))
      (node (ref "R118") (pin "2") (pinfunction "2_2") (pintype "passive"))
    )
    (net (code "15") (name "Net-(K1-Pad14)") (class "Default")
      (node (ref "K1") (pin "14") (pinfunction "14_14") (pintype "passive"))
      (node (ref "R117") (pin "2") (pinfunction "2_2") (pintype "passive"))
    )
    (net (code "16") (name "Net-(K1-Pad15)") (class "Default")
      (node (ref "K1") (pin "15") (pinfunction "15_15") (pintype "passive"))
      (node (ref "R116") (pin "2") (pinfunction "2_2") (pintype "passive"))
    )
    (net (code "17") (name "Net-(K1-Pad16)") (class "Default")
      (node (ref "K1") (pin "16") (pinfunction "16_16") (pintype "passive"))
      (node (ref "R115") (pin "2") (pinfunction "2_2") (pintype "passive"))
    )
    (net (code "18") (name "Net-(K1-Pad17)") (class "Default")
      (node (ref "K1") (pin "17") (pinfunction "17_17") (pintype "passive"))
      (node (ref "R114") (pin "2") (pinfunction "2_2") (pintype "passive"))
    )
    (net (code "19") (name "Net-(K1-Pad18)") (class "Default")
      (node (ref "K1") (pin "18") (pinfunction "18_18") (pintype "passive"))
      (node (ref "R113") (pin "2") (pinfunction "2_2") (pintype "passive"))
    )
    (net (code "20") (name "Net-(K1-Pad19)") (class "Default")
      (node (ref "K1") (pin "19") (pinfunction "19_19") (pintype "passive"))
      (node (ref "R112") (pin "2") (pinfunction "2_2") (pintype "passive"))
    )
    (net (code "21") (name "Net-(K1-Pad20)") (class "Default")
      (node (ref "K1") (pin "20") (pinfunction "20_20") (pintype "passive"))
      (node (ref "R111") (pin "2") (pinfunction "2_2") (pintype "passive"))
    )
    (net (code "22") (name "Net-(K1-Pad21)") (class "Default")
      (node (ref "K1") (pin "21") (pinfunction "21_21") (pintype "passive"))
      (node (ref "R110") (pin "2") (pinfunction "2_2") (pintype "passive"))
    )
    (net (code "23") (name "Net-(K1-Pad22)") (class "Default")
      (node (ref "K1") (pin "22") (pinfunction "22_22") (pintype "passive"))
      (node (ref "R109") (pin "2") (pinfunction "2_2") (pintype "passive"))
    )
    (net (code "24") (name "Net-(K1-Pad23)") (class "Default")
      (node (ref "K1") (pin "23") (pinfunction "23_23") (pintype "passive"))
      (node (ref "R108") (pin "2") (pinfunction "2_2") (pintype "passive"))
    )
    (net (code "25") (name "Net-(K1-Pad24)") (class "Default")
      (node (ref "K1") (pin "24") (pinfunction "24_24") (pintype "passive"))
      (node (ref "R107") (pin "2") (pinfunction "2_2") (pintype "passive"))
    )
    (net (code "26") (name "Net-(K1-Pad25)") (class "Default")
      (node (ref "K1") (pin "25") (pinfunction "25_25") (pintype "passive"))
      (node (ref "R106") (pin "2") (pinfunction "2_2") (pintype "passive"))
    )
    (net (code "27") (name "Net-(K1-Pad26)") (class "Default")
      (node (ref "K1") (pin "26") (pinfunction "26_26") (pintype "passive"))
      (node (ref "R105") (pin "2") (pinfunction "2_2") (pintype "passive"))
    )
    (net (code "28") (name "Net-(K1-Pad27)") (class "Default")
      (node (ref "K1") (pin "27") (pinfunction "27_27") (pintype "passive"))
      (node (ref "R104") (pin "2") (pinfunction "2_2") (pintype "passive"))
    )
    (net (code "29") (name "Net-(K1-Pad28)") (class "Default")
      (node (ref "K1") (pin "28") (pinfunction "28_28") (pintype "passive"))
      (node (ref "R103") (pin "2") (pinfunction "2_2") (pintype "passive"))
    )
    (net (code "30") (name "Net-(K1-Pad29)") (class "Default")
      (node (ref "K1") (pin "29") (pinfunction "29_29") (pintype "passive"))
      (node (ref "R102") (pin "2") (pinfunction "2_2") (pintype "passive"))
    )
    (net (code "31") (name "Net-(K1-Pad30)") (class "Default")
      (node (ref "K1") (pin "30") (pinfunction "30_30") (pintype "passive"))
      (node (ref "R101") (pin "2") (pinfunction "2_2") (pintype "passive"))
    )
    (net (code "32") (name "Net-(K1-Pad31)") (class "Default")
      (node (ref "K1") (pin "31") (pinfunction "31_31") (pintype "passive"))
      (node (ref "R100") (pin "2") (pinfunction "2_2") (pintype "passive"))
    )
    (net (code "33") (name "Net-(K1-Pad32)") (class "Default")
      (node (ref "K1") (pin "32") (pinfunction "32_32") (pintype "passive"))
      (node (ref "R99") (pin "2") (pinfunction "2_2") (pintype "passive"))
    )
    (net (code "34") (name "Net-(K4-Pad3)") (class "Default")
      (node (ref "K4") (pin "3") (pinfunction "3_3") (pintype "passive"))
      (node (ref "R68") (pin "1") (pinfunction "1_1") (pintype "passive"))
      (node (ref "R70") (pin "1") (pinfunction "1_1") (pintype "passive"))
      (node (ref "R72") (pin "1") (pinfunction "1_1") (pintype "passive"))
      (node (ref "R74") (pin "1") (pinfunction "1_1") (pintype "passive"))
      (node (ref "R76") (pin "1") (pinfunction "1_1") (pintype "passive"))
      (node (ref "R78") (pin "1") (pinfunction "1_1") (pintype "passive"))
      (node (ref "R80") (pin "1") (pinfunction "1_1") (pintype "passive"))
      (node (ref "R82") (pin "1") (pinfunction "1_1") (pintype "passive"))
      (node (ref "R84") (pin "1") (pinfunction "1_1") (pintype "passive"))
      (node (ref "R86") (pin "1") (pinfunction "1_1") (pintype "passive"))
      (node (ref "R88") (pin "1") (pinfunction "1_1") (pintype "passive"))
      (node (ref "R90") (pin "1") (pinfunction "1_1") (pintype "passive"))
      (node (ref "R92") (pin "1") (pinfunction "1_1") (pintype "passive"))
      (node (ref "R94") (pin "1") (pinfunction "1_1") (pintype "passive"))
      (node (ref "R96") (pin "1") (pinfunction "1_1") (pintype "passive"))
      (node (ref "R98") (pin "1") (pinfunction "1_1") (pintype "passive"))
    )
    (net (code "35") (name "Net-(U$1-VIN+)") (class "Default")
      (node (ref "R113") (pin "1") (pinfunction "1_1") (pintype "passive"))
      (node (ref "R84") (pin "2") (pinfunction "2_2") (pintype "passive"))
      (node (ref "U$1") (pin "3") (pinfunction "VIN+_3") (pintype "input"))
    )
    (net (code "36") (name "Net-(U$1-VIN-)") (class "Default")
      (node (ref "R114") (pin "1") (pinfunction "1_1") (pintype "passive"))
      (node (ref "R83") (pin "1") (pinfunction "1_1") (pintype "passive"))
      (node (ref "U$1") (pin "2") (pinfunction "VIN-_2") (pintype "input"))
    )
    (net (code "37") (name "Net-(U$1-VOUT)") (class "Default")
      (node (ref "R83") (pin "2") (pinfunction "2_2") (pintype "passive"))
      (node (ref "U$1") (pin "6") (pinfunction "VOUT_6") (pintype "output"))
      (node (ref "U1") (pin "1") (pinfunction "CH8_1") (pintype "input"))
    )
    (net (code "38") (name "Net-(U$2-VIN+)") (class "Default")
      (node (ref "R111") (pin "1") (pinfunction "1_1") (pintype "passive"))
      (node (ref "R86") (pin "2") (pinfunction "2_2") (pintype "passive"))
      (node (ref "U$2") (pin "3") (pinfunction "VIN+_3") (pintype "input"))
    )
    (net (code "39") (name "Net-(U$2-VIN-)") (class "Default")
      (node (ref "R112") (pin "1") (pinfunction "1_1") (pintype "passive"))
      (node (ref "R85") (pin "1") (pinfunction "1_1") (pintype "passive"))
      (node (ref "U$2") (pin "2") (pinfunction "VIN-_2") (pintype "input"))
    )
    (net (code "40") (name "Net-(U$2-VOUT)") (class "Default")
      (node (ref "R85") (pin "2") (pinfunction "2_2") (pintype "passive"))
      (node (ref "U$2") (pin "6") (pinfunction "VOUT_6") (pintype "output"))
      (node (ref "U1") (pin "2") (pinfunction "CH9_2") (pintype "input"))
    )
    (net (code "41") (name "Net-(U$3-VIN+)") (class "Default")
      (node (ref "R109") (pin "1") (pinfunction "1_1") (pintype "passive"))
      (node (ref "R88") (pin "2") (pinfunction "2_2") (pintype "passive"))
      (node (ref "U$3") (pin "3") (pinfunction "VIN+_3") (pintype "input"))
    )
    (net (code "42") (name "Net-(U$3-VIN-)") (class "Default")
      (node (ref "R110") (pin "1") (pinfunction "1_1") (pintype "passive"))
      (node (ref "R87") (pin "1") (pinfunction "1_1") (pintype "passive"))
      (node (ref "U$3") (pin "2") (pinfunction "VIN-_2") (pintype "input"))
    )
    (net (code "43") (name "Net-(U$3-VOUT)") (class "Default")
      (node (ref "R87") (pin "2") (pinfunction "2_2") (pintype "passive"))
      (node (ref "U$3") (pin "6") (pinfunction "VOUT_6") (pintype "output"))
      (node (ref "U1") (pin "3") (pinfunction "CH10_3") (pintype "input"))
    )
    (net (code "44") (name "Net-(U$4-VIN+)") (class "Default")
      (node (ref "R107") (pin "1") (pinfunction "1_1") (pintype "passive"))
      (node (ref "R90") (pin "2") (pinfunction "2_2") (pintype "passive"))
      (node (ref "U$4") (pin "3") (pinfunction "VIN+_3") (pintype "input"))
    )
    (net (code "45") (name "Net-(U$4-VIN-)") (class "Default")
      (node (ref "R108") (pin "1") (pinfunction "1_1") (pintype "passive"))
      (node (ref "R89") (pin "1") (pinfunction "1_1") (pintype "passive"))
      (node (ref "U$4") (pin "2") (pinfunction "VIN-_2") (pintype "input"))
    )
    (net (code "46") (name "Net-(U$4-VOUT)") (class "Default")
      (node (ref "R89") (pin "2") (pinfunction "2_2") (pintype "passive"))
      (node (ref "U$4") (pin "6") (pinfunction "VOUT_6") (pintype "output"))
      (node (ref "U1") (pin "4") (pinfunction "CH11_4") (pintype "input"))
    )
    (net (code "47") (name "Net-(U$5-VIN+)") (class "Default")
      (node (ref "R105") (pin "1") (pinfunction "1_1") (pintype "passive"))
      (node (ref "R92") (pin "2") (pinfunction "2_2") (pintype "passive"))
      (node (ref "U$5") (pin "3") (pinfunction "VIN+_3") (pintype "input"))
    )
    (net (code "48") (name "Net-(U$5-VIN-)") (class "Default")
      (node (ref "R106") (pin "1") (pinfunction "1_1") (pintype "passive"))
      (node (ref "R91") (pin "1") (pinfunction "1_1") (pintype "passive"))
      (node (ref "U$5") (pin "2") (pinfunction "VIN-_2") (pintype "input"))
    )
    (net (code "49") (name "Net-(U$5-VOUT)") (class "Default")
      (node (ref "R91") (pin "2") (pinfunction "2_2") (pintype "passive"))
      (node (ref "U$5") (pin "6") (pinfunction "VOUT_6") (pintype "output"))
      (node (ref "U1") (pin "5") (pinfunction "CH12_5") (pintype "input"))
    )
    (net (code "50") (name "Net-(U$6-VIN+)") (class "Default")
      (node (ref "R103") (pin "1") (pinfunction "1_1") (pintype "passive"))
      (node (ref "R94") (pin "2") (pinfunction "2_2") (pintype "passive"))
      (node (ref "U$6") (pin "3") (pinfunction "VIN+_3") (pintype "input"))
    )
    (net (code "51") (name "Net-(U$6-VIN-)") (class "Default")
      (node (ref "R104") (pin "1") (pinfunction "1_1") (pintype "passive"))
      (node (ref "R93") (pin "1") (pinfunction "1_1") (pintype "passive"))
      (node (ref "U$6") (pin "2") (pinfunction "VIN-_2") (pintype "input"))
    )
    (net (code "52") (name "Net-(U$6-VOUT)") (class "Default")
      (node (ref "R93") (pin "2") (pinfunction "2_2") (pintype "passive"))
      (node (ref "U$6") (pin "6") (pinfunction "VOUT_6") (pintype "output"))
      (node (ref "U1") (pin "6") (pinfunction "CH13_6") (pintype "input"))
    )
    (net (code "53") (name "Net-(U$7-VIN+)") (class "Default")
      (node (ref "R101") (pin "1") (pinfunction "1_1") (pintype "passive"))
      (node (ref "R96") (pin "2") (pinfunction "2_2") (pintype "passive"))
      (node (ref "U$7") (pin "3") (pinfunction "VIN+_3") (pintype "input"))
    )
    (net (code "54") (name "Net-(U$7-VIN-)") (class "Default")
      (node (ref "R102") (pin "1") (pinfunction "1_1") (pintype "passive"))
      (node (ref "R95") (pin "1") (pinfunction "1_1") (pintype "passive"))
      (node (ref "U$7") (pin "2") (pinfunction "VIN-_2") (pintype "input"))
    )
    (net (code "55") (name "Net-(U$7-VOUT)") (class "Default")
      (node (ref "R95") (pin "2") (pinfunction "2_2") (pintype "passive"))
      (node (ref "U$7") (pin "6") (pinfunction "VOUT_6") (pintype "output"))
      (node (ref "U1") (pin "7") (pinfunction "CH14_7") (pintype "input"))
    )
    (net (code "56") (name "Net-(U$8-VIN+)") (class "Default")
      (node (ref "R115") (pin "1") (pinfunction "1_1") (pintype "passive"))
      (node (ref "R82") (pin "2") (pinfunction "2_2") (pintype "passive"))
      (node (ref "U$8") (pin "3") (pinfunction "VIN+_3") (pintype "input"))
    )
    (net (code "57") (name "Net-(U$8-VIN-)") (class "Default")
      (node (ref "R116") (pin "1") (pinfunction "1_1") (pintype "passive"))
      (node (ref "R81") (pin "1") (pinfunction "1_1") (pintype "passive"))
      (node (ref "U$8") (pin "2") (pinfunction "VIN-_2") (pintype "input"))
    )
    (net (code "58") (name "Net-(U$8-VOUT)") (class "Default")
      (node (ref "R81") (pin "2") (pinfunction "2_2") (pintype "passive"))
      (node (ref "U$8") (pin "6") (pinfunction "VOUT_6") (pintype "output"))
      (node (ref "U1") (pin "28") (pinfunction "CH7_28") (pintype "input"))
    )
    (net (code "59") (name "Net-(U$9-VIN+)") (class "Default")
      (node (ref "R117") (pin "1") (pinfunction "1_1") (pintype "passive"))
      (node (ref "R80") (pin "2") (pinfunction "2_2") (pintype "passive"))
      (node (ref "U$9") (pin "3") (pinfunction "VIN+_3") (pintype "input"))
    )
    (net (code "60") (name "Net-(U$9-VIN-)") (class "Default")
      (node (ref "R118") (pin "1") (pinfunction "1_1") (pintype "passive"))
      (node (ref "R79") (pin "1") (pinfunction "1_1") (pintype "passive"))
      (node (ref "U$9") (pin "2") (pinfunction "VIN-_2") (pintype "input"))
    )
    (net (code "61") (name "Net-(U$9-VOUT)") (class "Default")
      (node (ref "R79") (pin "2") (pinfunction "2_2") (pintype "passive"))
      (node (ref "U$9") (pin "6") (pinfunction "VOUT_6") (pintype "output"))
      (node (ref "U1") (pin "27") (pinfunction "CH6_27") (pintype "input"))
    )
    (net (code "62") (name "Net-(U$10-VIN+)") (class "Default")
      (node (ref "R119") (pin "1") (pinfunction "1_1") (pintype "passive"))
      (node (ref "R78") (pin "2") (pinfunction "2_2") (pintype "passive"))
      (node (ref "U$10") (pin "3") (pinfunction "VIN+_3") (pintype "input"))
    )
    (net (code "63") (name "Net-(U$10-VIN-)") (class "Default")
      (node (ref "R120") (pin "1") (pinfunction "1_1") (pintype "passive"))
      (node (ref "R77") (pin "1") (pinfunction "1_1") (pintype "passive"))
      (node (ref "U$10") (pin "2") (pinfunction "VIN-_2") (pintype "input"))
    )
    (net (code "64") (name "Net-(U$10-VOUT)") (class "Default")
      (node (ref "R77") (pin "2") (pinfunction "2_2") (pintype "passive"))
      (node (ref "U$10") (pin "6") (pinfunction "VOUT_6") (pintype "output"))
      (node (ref "U1") (pin "26") (pinfunction "CH5_26") (pintype "input"))
    )
    (net (code "65") (name "Net-(U$11-VIN+)") (class "Default")
      (node (ref "R121") (pin "1") (pinfunction "1_1") (pintype "passive"))
      (node (ref "R76") (pin "2") (pinfunction "2_2") (pintype "passive"))
      (node (ref "U$11") (pin "3") (pinfunction "VIN+_3") (pintype "input"))
    )
    (net (code "66") (name "Net-(U$11-VIN-)") (class "Default")
      (node (ref "R122") (pin "1") (pinfunction "1_1") (pintype "passive"))
      (node (ref "R75") (pin "1") (pinfunction "1_1") (pintype "passive"))
      (node (ref "U$11") (pin "2") (pinfunction "VIN-_2") (pintype "input"))
    )
    (net (code "67") (name "Net-(U$11-VOUT)") (class "Default")
      (node (ref "R75") (pin "2") (pinfunction "2_2") (pintype "passive"))
      (node (ref "U$11") (pin "6") (pinfunction "VOUT_6") (pintype "output"))
      (node (ref "U1") (pin "25") (pinfunction "CH4_25") (pintype "input"))
    )
    (net (code "68") (name "Net-(U$12-VIN+)") (class "Default")
      (node (ref "R123") (pin "1") (pinfunction "1_1") (pintype "passive"))
      (node (ref "R74") (pin "2") (pinfunction "2_2") (pintype "passive"))
      (node (ref "U$12") (pin "3") (pinfunction "VIN+_3") (pintype "input"))
    )
    (net (code "69") (name "Net-(U$12-VIN-)") (class "Default")
      (node (ref "R124") (pin "1") (pinfunction "1_1") (pintype "passive"))
      (node (ref "R73") (pin "1") (pinfunction "1_1") (pintype "passive"))
      (node (ref "U$12") (pin "2") (pinfunction "VIN-_2") (pintype "input"))
    )
    (net (code "70") (name "Net-(U$12-VOUT)") (class "Default")
      (node (ref "R73") (pin "2") (pinfunction "2_2") (pintype "passive"))
      (node (ref "U$12") (pin "6") (pinfunction "VOUT_6") (pintype "output"))
      (node (ref "U1") (pin "24") (pinfunction "CH3_24") (pintype "input"))
    )
    (net (code "71") (name "Net-(U$13-VIN+)") (class "Default")
      (node (ref "R98") (pin "2") (pinfunction "2_2") (pintype "passive"))
      (node (ref "R99") (pin "1") (pinfunction "1_1") (pintype "passive"))
      (node (ref "U$13") (pin "3") (pinfunction "VIN+_3") (pintype "input"))
    )
    (net (code "72") (name "Net-(U$13-VIN-)") (class "Default")
      (node (ref "R100") (pin "1") (pinfunction "1_1") (pintype "passive"))
      (node (ref "R97") (pin "1") (pinfunction "1_1") (pintype "passive"))
      (node (ref "U$13") (pin "2") (pinfunction "VIN-_2") (pintype "input"))
    )
    (net (code "73") (name "Net-(U$13-VOUT)") (class "Default")
      (node (ref "R97") (pin "2") (pinfunction "2_2") (pintype "passive"))
      (node (ref "U$13") (pin "6") (pinfunction "VOUT_6") (pintype "output"))
      (node (ref "U1") (pin "8") (pinfunction "CH15_8") (pintype "input"))
    )
    (net (code "74") (name "Net-(U$14-VIN+)") (class "Default")
      (node (ref "R125") (pin "1") (pinfunction "1_1") (pintype "passive"))
      (node (ref "R72") (pin "2") (pinfunction "2_2") (pintype "passive"))
      (node (ref "U$14") (pin "3") (pinfunction "VIN+_3") (pintype "input"))
    )
    (net (code "75") (name "Net-(U$14-VIN-)") (class "Default")
      (node (ref "R126") (pin "1") (pinfunction "1_1") (pintype "passive"))
      (node (ref "R71") (pin "1") (pinfunction "1_1") (pintype "passive"))
      (node (ref "U$14") (pin "2") (pinfunction "VIN-_2") (pintype "input"))
    )
    (net (code "76") (name "Net-(U$14-VOUT)") (class "Default")
      (node (ref "R71") (pin "2") (pinfunction "2_2") (pintype "passive"))
      (node (ref "U$14") (pin "6") (pinfunction "VOUT_6") (pintype "output"))
      (node (ref "U1") (pin "23") (pinfunction "CH2_23") (pintype "input"))
    )
    (net (code "77") (name "Net-(U$15-VIN+)") (class "Default")
      (node (ref "R127") (pin "1") (pinfunction "1_1") (pintype "passive"))
      (node (ref "R70") (pin "2") (pinfunction "2_2") (pintype "passive"))
      (node (ref "U$15") (pin "3") (pinfunction "VIN+_3") (pintype "input"))
    )
    (net (code "78") (name "Net-(U$15-VIN-)") (class "Default")
      (node (ref "R128") (pin "1") (pinfunction "1_1") (pintype "passive"))
      (node (ref "R69") (pin "1") (pinfunction "1_1") (pintype "passive"))
      (node (ref "U$15") (pin "2") (pinfunction "VIN-_2") (pintype "input"))
    )
    (net (code "79") (name "Net-(U$15-VOUT)") (class "Default")
      (node (ref "R69") (pin "2") (pinfunction "2_2") (pintype "passive"))
      (node (ref "U$15") (pin "6") (pinfunction "VOUT_6") (pintype "output"))
      (node (ref "U1") (pin "22") (pinfunction "CH1_22") (pintype "input"))
    )
    (net (code "80") (name "Net-(U$16-VIN+)") (class "Default")
      (node (ref "R129") (pin "1") (pinfunction "1_1") (pintype "passive"))
      (node (ref "R68") (pin "2") (pinfunction "2_2") (pintype "passive"))
      (node (ref "U$16") (pin "3") (pinfunction "VIN+_3") (pintype "input"))
    )
    (net (code "81") (name "Net-(U$16-VIN-)") (class "Default")
      (node (ref "R130") (pin "1") (pinfunction "1_1") (pintype "passive"))
      (node (ref "R67") (pin "1") (pinfunction "1_1") (pintype "passive"))
      (node (ref "U$16") (pin "2") (pinfunction "VIN-_2") (pintype "input"))
    )
    (net (code "82") (name "Net-(U$16-VOUT)") (class "Default")
      (node (ref "R67") (pin "2") (pinfunction "2_2") (pintype "passive"))
      (node (ref "U$16") (pin "6") (pinfunction "VOUT_6") (pintype "output"))
      (node (ref "U1") (pin "21") (pinfunction "CH0_21") (pintype "input"))
    )
    (net (code "83") (name "Net-(U1-F0)") (class "Default")
      (node (ref "K4") (pin "1") (pinfunction "1_1") (pintype "passive"))
      (node (ref "U1") (pin "19") (pinfunction "F0_19") (pintype "input"))
    )
    (net (code "84") (name "Net-(U1-SCK)") (class "Default")
      (node (ref "K4") (pin "4") (pinfunction "4_4") (pintype "passive"))
      (node (ref "U1") (pin "18") (pinfunction "SCK_18") (pintype "bidirectional"))
    )
    (net (code "85") (name "Net-(U1-SDI)") (class "Default")
      (node (ref "K4") (pin "8") (pinfunction "8_8") (pintype "passive"))
      (node (ref "U1") (pin "20") (pinfunction "SDI_20") (pintype "input"))
    )
    (net (code "86") (name "Net-(U1-SDO)") (class "Default")
      (node (ref "K4") (pin "12") (pinfunction "12_12") (pintype "passive"))
      (node (ref "U1") (pin "17") (pinfunction "SDO_17") (pintype "output"))
    )
    (net (code "87") (name "Net-(U1-~{CS})") (class "Default")
      (node (ref "K4") (pin "5") (pinfunction "5_5") (pintype "passive"))
      (node (ref "U1") (pin "16") (pinfunction "~{CS}_16") (pintype "input"))
    )
    (net (code "88") (name "Net-(U2-COMMON_IN{slash}OUT)") (class "Default")
      (node (ref "K4") (pin "34") (pinfunction "34_34") (pintype "passive"))
      (node (ref "U2") (pin "1") (pinfunction "COMMON_IN/OUT_1") (pintype "bidirectional"))
      (node (ref "U4") (pin "1") (pinfunction "COMMON_IN/OUT_1") (pintype "bidirectional"))
    )
    (net (code "89") (name "Net-(U2-I0)") (class "Default")
      (node (ref "K2") (pin "1") (pinfunction "1_1") (pintype "passive"))
      (node (ref "U2") (pin "9") (pinfunction "I0_9") (pintype "input"))
    )
    (net (code "90") (name "Net-(U2-I1)") (class "Default")
      (node (ref "K2") (pin "3") (pinfunction "3_3") (pintype "passive"))
      (node (ref "U2") (pin "8") (pinfunction "I1_8") (pintype "input"))
    )
    (net (code "91") (name "Net-(U2-I2)") (class "Default")
      (node (ref "K2") (pin "5") (pinfunction "5_5") (pintype "passive"))
      (node (ref "U2") (pin "7") (pinfunction "I2_7") (pintype "input"))
    )
    (net (code "92") (name "Net-(U2-I3)") (class "Default")
      (node (ref "K2") (pin "7") (pinfunction "7_7") (pintype "passive"))
      (node (ref "U2") (pin "6") (pinfunction "I3_6") (pintype "input"))
    )
    (net (code "93") (name "Net-(U2-I4)") (class "Default")
      (node (ref "K2") (pin "9") (pinfunction "9_9") (pintype "passive"))
      (node (ref "U2") (pin "5") (pinfunction "I4_5") (pintype "input"))
    )
    (net (code "94") (name "Net-(U2-I5)") (class "Default")
      (node (ref "K2") (pin "11") (pinfunction "11_11") (pintype "passive"))
      (node (ref "U2") (pin "4") (pinfunction "I5_4") (pintype "input"))
    )
    (net (code "95") (name "Net-(U2-I6)") (class "Default")
      (node (ref "K2") (pin "13") (pinfunction "13_13") (pintype "passive"))
      (node (ref "U2") (pin "3") (pinfunction "I6_3") (pintype "input"))
    )
    (net (code "96") (name "Net-(U2-I7)") (class "Default")
      (node (ref "K2") (pin "15") (pinfunction "15_15") (pintype "passive"))
      (node (ref "U2") (pin "2") (pinfunction "I7_2") (pintype "input"))
    )
    (net (code "97") (name "Net-(U2-I8)") (class "Default")
      (node (ref "K2") (pin "17") (pinfunction "17_17") (pintype "passive"))
      (node (ref "U2") (pin "23") (pinfunction "I8_23") (pintype "input"))
    )
    (net (code "98") (name "Net-(U2-I9)") (class "Default")
      (node (ref "K2") (pin "19") (pinfunction "19_19") (pintype "passive"))
      (node (ref "U2") (pin "22") (pinfunction "I9_22") (pintype "input"))
    )
    (net (code "99") (name "Net-(U2-I10)") (class "Default")
      (node (ref "K2") (pin "21") (pinfunction "21_21") (pintype "passive"))
      (node (ref "U2") (pin "21") (pinfunction "I10_21") (pintype "input"))
    )
    (net (code "100") (name "Net-(U2-I11)") (class "Default")
      (node (ref "K2") (pin "23") (pinfunction "23_23") (pintype "passive"))
      (node (ref "U2") (pin "20") (pinfunction "I11_20") (pintype "input"))
    )
    (net (code "101") (name "Net-(U2-I12)") (class "Default")
      (node (ref "K2") (pin "25") (pinfunction "25_25") (pintype "passive"))
      (node (ref "U2") (pin "19") (pinfunction "I12_19") (pintype "input"))
    )
    (net (code "102") (name "Net-(U2-I13)") (class "Default")
      (node (ref "K2") (pin "27") (pinfunction "27_27") (pintype "passive"))
      (node (ref "U2") (pin "18") (pinfunction "I13_18") (pintype "input"))
    )
    (net (code "103") (name "Net-(U2-I14)") (class "Default")
      (node (ref "K2") (pin "29") (pinfunction "29_29") (pintype "passive"))
      (node (ref "U2") (pin "17") (pinfunction "I14_17") (pintype "input"))
    )
    (net (code "104") (name "Net-(U2-I15)") (class "Default")
      (node (ref "K2") (pin "31") (pinfunction "31_31") (pintype "passive"))
      (node (ref "U2") (pin "16") (pinfunction "I15_16") (pintype "input"))
    )
    (net (code "105") (name "Net-(U2-S0)") (class "Default")
      (node (ref "K4") (pin "24") (pinfunction "24_24") (pintype "passive"))
      (node (ref "U2") (pin "10") (pinfunction "S0_10") (pintype "input"))
      (node (ref "U3") (pin "10") (pinfunction "S0_10") (pintype "input"))
      (node (ref "U4") (pin "10") (pinfunction "S0_10") (pintype "input"))
      (node (ref "U5") (pin "10") (pinfunction "S0_10") (pintype "input"))
    )
    (net (code "106") (name "Net-(U2-S1)") (class "Default")
      (node (ref "K4") (pin "26") (pinfunction "26_26") (pintype "passive"))
      (node (ref "U2") (pin "11") (pinfunction "S1_11") (pintype "input"))
      (node (ref "U3") (pin "11") (pinfunction "S1_11") (pintype "input"))
      (node (ref "U4") (pin "11") (pinfunction "S1_11") (pintype "input"))
      (node (ref "U5") (pin "11") (pinfunction "S1_11") (pintype "input"))
    )
    (net (code "107") (name "Net-(U2-S2)") (class "Default")
      (node (ref "K4") (pin "28") (pinfunction "28_28") (pintype "passive"))
      (node (ref "U2") (pin "14") (pinfunction "S2_14") (pintype "input"))
      (node (ref "U3") (pin "14") (pinfunction "S2_14") (pintype "input"))
      (node (ref "U4") (pin "14") (pinfunction "S2_14") (pintype "input"))
      (node (ref "U5") (pin "14") (pinfunction "S2_14") (pintype "input"))
    )
    (net (code "108") (name "Net-(U2-S3)") (class "Default")
      (node (ref "K4") (pin "30") (pinfunction "30_30") (pintype "passive"))
      (node (ref "U2") (pin "13") (pinfunction "S3_13") (pintype "input"))
      (node (ref "U3") (pin "13") (pinfunction "S3_13") (pintype "input"))
      (node (ref "U4") (pin "13") (pinfunction "S3_13") (pintype "input"))
      (node (ref "U5") (pin "13") (pinfunction "S3_13") (pintype "input"))
    )
    (net (code "109") (name "Net-(U2-~{E})") (class "Default")
      (node (ref "K4") (pin "2") (pinfunction "2_2") (pintype "passive"))
      (node (ref "U2") (pin "15") (pinfunction "~{E}_15") (pintype "input"))
      (node (ref "U3") (pin "15") (pinfunction "~{E}_15") (pintype "input"))
    )
    (net (code "110") (name "Net-(U3-COMMON_IN{slash}OUT)") (class "Default")
      (node (ref "K4") (pin "33") (pinfunction "33_33") (pintype "passive"))
      (node (ref "U3") (pin "1") (pinfunction "COMMON_IN/OUT_1") (pintype "bidirectional"))
      (node (ref "U5") (pin "1") (pinfunction "COMMON_IN/OUT_1") (pintype "bidirectional"))
    )
    (net (code "111") (name "Net-(U3-I0)") (class "Default")
      (node (ref "K2") (pin "2") (pinfunction "2_2") (pintype "passive"))
      (node (ref "U3") (pin "9") (pinfunction "I0_9") (pintype "input"))
    )
    (net (code "112") (name "Net-(U3-I1)") (class "Default")
      (node (ref "K2") (pin "4") (pinfunction "4_4") (pintype "passive"))
      (node (ref "U3") (pin "8") (pinfunction "I1_8") (pintype "input"))
    )
    (net (code "113") (name "Net-(U3-I2)") (class "Default")
      (node (ref "K2") (pin "6") (pinfunction "6_6") (pintype "passive"))
      (node (ref "U3") (pin "7") (pinfunction "I2_7") (pintype "input"))
    )
    (net (code "114") (name "Net-(U3-I3)") (class "Default")
      (node (ref "K2") (pin "8") (pinfunction "8_8") (pintype "passive"))
      (node (ref "U3") (pin "6") (pinfunction "I3_6") (pintype "input"))
    )
    (net (code "115") (name "Net-(U3-I4)") (class "Default")
      (node (ref "K2") (pin "10") (pinfunction "10_10") (pintype "passive"))
      (node (ref "U3") (pin "5") (pinfunction "I4_5") (pintype "input"))
    )
    (net (code "116") (name "Net-(U3-I5)") (class "Default")
      (node (ref "K2") (pin "12") (pinfunction "12_12") (pintype "passive"))
      (node (ref "U3") (pin "4") (pinfunction "I5_4") (pintype "input"))
    )
    (net (code "117") (name "Net-(U3-I6)") (class "Default")
      (node (ref "K2") (pin "14") (pinfunction "14_14") (pintype "passive"))
      (node (ref "U3") (pin "3") (pinfunction "I6_3") (pintype "input"))
    )
    (net (code "118") (name "Net-(U3-I7)") (class "Default")
      (node (ref "K2") (pin "16") (pinfunction "16_16") (pintype "passive"))
      (node (ref "U3") (pin "2") (pinfunction "I7_2") (pintype "input"))
    )
    (net (code "119") (name "Net-(U3-I8)") (class "Default")
      (node (ref "K2") (pin "18") (pinfunction "18_18") (pintype "passive"))
      (node (ref "U3") (pin "23") (pinfunction "I8_23") (pintype "input"))
    )
    (net (code "120") (name "Net-(U3-I9)") (class "Default")
      (node (ref "K2") (pin "20") (pinfunction "20_20") (pintype "passive"))
      (node (ref "U3") (pin "22") (pinfunction "I9_22") (pintype "input"))
    )
    (net (code "121") (name "Net-(U3-I10)") (class "Default")
      (node (ref "K2") (pin "22") (pinfunction "22_22") (pintype "passive"))
      (node (ref "U3") (pin "21") (pinfunction "I10_21") (pintype "input"))
    )
    (net (code "122") (name "Net-(U3-I11)") (class "Default")
      (node (ref "K2") (pin "24") (pinfunction "24_24") (pintype "passive"))
      (node (ref "U3") (pin "20") (pinfunction "I11_20") (pintype "input"))
    )
    (net (code "123") (name "Net-(U3-I12)") (class "Default")
      (node (ref "K2") (pin "26") (pinfunction "26_26") (pintype "passive"))
      (node (ref "U3") (pin "19") (pinfunction "I12_19") (pintype "input"))
    )
    (net (code "124") (name "Net-(U3-I13)") (class "Default")
      (node (ref "K2") (pin "28") (pinfunction "28_28") (pintype "passive"))
      (node (ref "U3") (pin "18") (pinfunction "I13_18") (pintype "input"))
    )
    (net (code "125") (name "Net-(U3-I14)") (class "Default")
      (node (ref "K2") (pin "30") (pinfunction "30_30") (pintype "passive"))
      (node (ref "U3") (pin "17") (pinfunction "I14_17") (pintype "input"))
    )
    (net (code "126") (name "Net-(U3-I15)") (class "Default")
      (node (ref "K2") (pin "32") (pinfunction "32_32") (pintype "passive"))
      (node (ref "U3") (pin "16") (pinfunction "I15_16") (pintype "input"))
    )
    (net (code "127") (name "Net-(U4-I0)") (class "Default")
      (node (ref "K3") (pin "1") (pinfunction "1_1") (pintype "passive"))
      (node (ref "U4") (pin "9") (pinfunction "I0_9") (pintype "input"))
    )
    (net (code "128") (name "Net-(U4-I1)") (class "Default")
      (node (ref "K3") (pin "3") (pinfunction "3_3") (pintype "passive"))
      (node (ref "U4") (pin "8") (pinfunction "I1_8") (pintype "input"))
    )
    (net (code "129") (name "Net-(U4-I2)") (class "Default")
      (node (ref "K3") (pin "5") (pinfunction "5_5") (pintype "passive"))
      (node (ref "U4") (pin "7") (pinfunction "I2_7") (pintype "input"))
    )
    (net (code "130") (name "Net-(U4-I3)") (class "Default")
      (node (ref "K3") (pin "7") (pinfunction "7_7") (pintype "passive"))
      (node (ref "U4") (pin "6") (pinfunction "I3_6") (pintype "input"))
    )
    (net (code "131") (name "Net-(U4-I4)") (class "Default")
      (node (ref "K3") (pin "9") (pinfunction "9_9") (pintype "passive"))
      (node (ref "U4") (pin "5") (pinfunction "I4_5") (pintype "input"))
    )
    (net (code "132") (name "Net-(U4-I5)") (class "Default")
      (node (ref "K3") (pin "11") (pinfunction "11_11") (pintype "passive"))
      (node (ref "U4") (pin "4") (pinfunction "I5_4") (pintype "input"))
    )
    (net (code "133") (name "Net-(U4-I6)") (class "Default")
      (node (ref "K3") (pin "13") (pinfunction "13_13") (pintype "passive"))
      (node (ref "U4") (pin "3") (pinfunction "I6_3") (pintype "input"))
    )
    (net (code "134") (name "Net-(U4-I7)") (class "Default")
      (node (ref "K3") (pin "15") (pinfunction "15_15") (pintype "passive"))
      (node (ref "U4") (pin "2") (pinfunction "I7_2") (pintype "input"))
    )
    (net (code "135") (name "Net-(U4-I8)") (class "Default")
      (node (ref "K3") (pin "17") (pinfunction "17_17") (pintype "passive"))
      (node (ref "U4") (pin "23") (pinfunction "I8_23") (pintype "input"))
    )
    (net (code "136") (name "Net-(U4-I9)") (class "Default")
      (node (ref "K3") (pin "19") (pinfunction "19_19") (pintype "passive"))
      (node (ref "U4") (pin "22") (pinfunction "I9_22") (pintype "input"))
    )
    (net (code "137") (name "Net-(U4-I10)") (class "Default")
      (node (ref "K3") (pin "21") (pinfunction "21_21") (pintype "passive"))
      (node (ref "U4") (pin "21") (pinfunction "I10_21") (pintype "input"))
    )
    (net (code "138") (name "Net-(U4-I11)") (class "Default")
      (node (ref "K3") (pin "23") (pinfunction "23_23") (pintype "passive"))
      (node (ref "U4") (pin "20") (pinfunction "I11_20") (pintype "input"))
    )
    (net (code "139") (name "Net-(U4-I12)") (class "Default")
      (node (ref "K3") (pin "25") (pinfunction "25_25") (pintype "passive"))
      (node (ref "U4") (pin "19") (pinfunction "I12_19") (pintype "input"))
    )
    (net (code "140") (name "Net-(U4-I13)") (class "Default")
      (node (ref "K3") (pin "27") (pinfunction "27_27") (pintype "passive"))
      (node (ref "U4") (pin "18") (pinfunction "I13_18") (pintype "input"))
    )
    (net (code "141") (name "Net-(U4-I14)") (class "Default")
      (node (ref "K3") (pin "29") (pinfunction "29_29") (pintype "passive"))
      (node (ref "U4") (pin "17") (pinfunction "I14_17") (pintype "input"))
    )
    (net (code "142") (name "Net-(U4-I15)") (class "Default")
      (node (ref "K3") (pin "31") (pinfunction "31_31") (pintype "passive"))
      (node (ref "U4") (pin "16") (pinfunction "I15_16") (pintype "input"))
    )
    (net (code "143") (name "Net-(U4-~{E})") (class "Default")
      (node (ref "K4") (pin "22") (pinfunction "22_22") (pintype "passive"))
      (node (ref "U4") (pin "15") (pinfunction "~{E}_15") (pintype "input"))
      (node (ref "U5") (pin "15") (pinfunction "~{E}_15") (pintype "input"))
    )
    (net (code "144") (name "Net-(U5-I0)") (class "Default")
      (node (ref "K3") (pin "2") (pinfunction "2_2") (pintype "passive"))
      (node (ref "U5") (pin "9") (pinfunction "I0_9") (pintype "input"))
    )
    (net (code "145") (name "Net-(U5-I1)") (class "Default")
      (node (ref "K3") (pin "4") (pinfunction "4_4") (pintype "passive"))
      (node (ref "U5") (pin "8") (pinfunction "I1_8") (pintype "input"))
    )
    (net (code "146") (name "Net-(U5-I2)") (class "Default")
      (node (ref "K3") (pin "6") (pinfunction "6_6") (pintype "passive"))
      (node (ref "U5") (pin "7") (pinfunction "I2_7") (pintype "input"))
    )
    (net (code "147") (name "Net-(U5-I3)") (class "Default")
      (node (ref "K3") (pin "8") (pinfunction "8_8") (pintype "passive"))
      (node (ref "U5") (pin "6") (pinfunction "I3_6") (pintype "input"))
    )
    (net (code "148") (name "Net-(U5-I4)") (class "Default")
      (node (ref "K3") (pin "10") (pinfunction "10_10") (pintype "passive"))
      (node (ref "U5") (pin "5") (pinfunction "I4_5") (pintype "input"))
    )
    (net (code "149") (name "Net-(U5-I5)") (class "Default")
      (node (ref "K3") (pin "12") (pinfunction "12_12") (pintype "passive"))
      (node (ref "U5") (pin "4") (pinfunction "I5_4") (pintype "input"))
    )
    (net (code "150") (name "Net-(U5-I6)") (class "Default")
      (node (ref "K3") (pin "14") (pinfunction "14_14") (pintype "passive"))
      (node (ref "U5") (pin "3") (pinfunction "I6_3") (pintype "input"))
    )
    (net (code "151") (name "Net-(U5-I7)") (class "Default")
      (node (ref "K3") (pin "16") (pinfunction "16_16") (pintype "passive"))
      (node (ref "U5") (pin "2") (pinfunction "I7_2") (pintype "input"))
    )
    (net (code "152") (name "Net-(U5-I8)") (class "Default")
      (node (ref "K3") (pin "18") (pinfunction "18_18") (pintype "passive"))
      (node (ref "U5") (pin "23") (pinfunction "I8_23") (pintype "input"))
    )
    (net (code "153") (name "Net-(U5-I9)") (class "Default")
      (node (ref "K3") (pin "20") (pinfunction "20_20") (pintype "passive"))
      (node (ref "U5") (pin "22") (pinfunction "I9_22") (pintype "input"))
    )
    (net (code "154") (name "Net-(U5-I10)") (class "Default")
      (node (ref "K3") (pin "22") (pinfunction "22_22") (pintype "passive"))
      (node (ref "U5") (pin "21") (pinfunction "I10_21") (pintype "input"))
    )
    (net (code "155") (name "Net-(U5-I11)") (class "Default")
      (node (ref "K3") (pin "24") (pinfunction "24_24") (pintype "passive"))
      (node (ref "U5") (pin "20") (pinfunction "I11_20") (pintype "input"))
    )
    (net (code "156") (name "Net-(U5-I12)") (class "Default")
      (node (ref "K3") (pin "26") (pinfunction "26_26") (pintype "passive"))
      (node (ref "U5") (pin "19") (pinfunction "I12_19") (pintype "input"))
    )
    (net (code "157") (name "Net-(U5-I13)") (class "Default")
      (node (ref "K3") (pin "28") (pinfunction "28_28") (pintype "passive"))
      (node (ref "U5") (pin "18") (pinfunction "I13_18") (pintype "input"))
    )
    (net (code "158") (name "Net-(U5-I14)") (class "Default")
      (node (ref "K3") (pin "30") (pinfunction "30_30") (pintype "passive"))
      (node (ref "U5") (pin "17") (pinfunction "I14_17") (pintype "input"))
    )
    (net (code "159") (name "Net-(U5-I15)") (class "Default")
      (node (ref "K3") (pin "32") (pinfunction "32_32") (pintype "passive"))
      (node (ref "U5") (pin "16") (pinfunction "I15_16") (pintype "input"))
    )
    (net (code "160") (name "VCC") (class "Default")
      (node (ref "C3") (pin "1") (pinfunction "1_1") (pintype "passive"))
      (node (ref "C4") (pin "1") (pinfunction "1_1") (pintype "passive"))
      (node (ref "K4") (pin "14") (pinfunction "14_14") (pintype "passive"))
      (node (ref "U$1") (pin "7") (pinfunction "VDD_7") (pintype "power_in"))
      (node (ref "U$10") (pin "7") (pinfunction "VDD_7") (pintype "power_in"))
      (node (ref "U$11") (pin "7") (pinfunction "VDD_7") (pintype "power_in"))
      (node (ref "U$12") (pin "7") (pinfunction "VDD_7") (pintype "power_in"))
      (node (ref "U$13") (pin "7") (pinfunction "VDD_7") (pintype "power_in"))
      (node (ref "U$14") (pin "7") (pinfunction "VDD_7") (pintype "power_in"))
      (node (ref "U$15") (pin "7") (pinfunction "VDD_7") (pintype "power_in"))
      (node (ref "U$16") (pin "7") (pinfunction "VDD_7") (pintype "power_in"))
      (node (ref "U$2") (pin "7") (pinfunction "VDD_7") (pintype "power_in"))
      (node (ref "U$3") (pin "7") (pinfunction "VDD_7") (pintype "power_in"))
      (node (ref "U$4") (pin "7") (pinfunction "VDD_7") (pintype "power_in"))
      (node (ref "U$5") (pin "7") (pinfunction "VDD_7") (pintype "power_in"))
      (node (ref "U$6") (pin "7") (pinfunction "VDD_7") (pintype "power_in"))
      (node (ref "U$7") (pin "7") (pinfunction "VDD_7") (pintype "power_in"))
      (node (ref "U$8") (pin "7") (pinfunction "VDD_7") (pintype "power_in"))
      (node (ref "U$9") (pin "7") (pinfunction "VDD_7") (pintype "power_in"))
      (node (ref "U1") (pin "11") (pinfunction "REF+_11") (pintype "input"))
      (node (ref "U1") (pin "9") (pinfunction "VCC_9") (pintype "power_in"))
      (node (ref "U2") (pin "24") (pinfunction "VCC_24") (pintype "power_in"))
      (node (ref "U3") (pin "24") (pinfunction "VCC_24") (pintype "power_in"))
      (node (ref "U4") (pin "24") (pinfunction "VCC_24") (pintype "power_in"))
      (node (ref "U5") (pin "24") (pinfunction "VCC_24") (pintype "power_in"))
    )
    (net (code "161") (name "unconnected-(K1-Pad33)") (class "Default")
      (node (ref "K1") (pin "33") (pinfunction "33_33") (pintype "passive"))
    )
    (net (code "162") (name "unconnected-(K1-Pad34)") (class "Default")
      (node (ref "K1") (pin "34") (pinfunction "34_34") (pintype "passive"))
    )
    (net (code "163") (name "unconnected-(K2-Pad33)") (class "Default")
      (node (ref "K2") (pin "33") (pinfunction "33_33") (pintype "passive"))
    )
    (net (code "164") (name "unconnected-(K2-Pad34)") (class "Default")
      (node (ref "K2") (pin "34") (pinfunction "34_34") (pintype "passive"))
    )
    (net (code "165") (name "unconnected-(K3-Pad33)") (class "Default")
      (node (ref "K3") (pin "33") (pinfunction "33_33") (pintype "passive"))
    )
    (net (code "166") (name "unconnected-(K3-Pad34)") (class "Default")
      (node (ref "K3") (pin "34") (pinfunction "34_34") (pintype "passive"))
    )
    (net (code "167") (name "unconnected-(K4-Pad6)") (class "Default")
      (node (ref "K4") (pin "6") (pinfunction "6_6") (pintype "passive"))
    )
    (net (code "168") (name "unconnected-(K4-Pad7)") (class "Default")
      (node (ref "K4") (pin "7") (pinfunction "7_7") (pintype "passive"))
    )
    (net (code "169") (name "unconnected-(K4-Pad9)") (class "Default")
      (node (ref "K4") (pin "9") (pinfunction "9_9") (pintype "passive"))
    )
    (net (code "170") (name "unconnected-(K4-Pad10)") (class "Default")
      (node (ref "K4") (pin "10") (pinfunction "10_10") (pintype "passive"))
    )
    (net (code "171") (name "unconnected-(K4-Pad11)") (class "Default")
      (node (ref "K4") (pin "11") (pinfunction "11_11") (pintype "passive"))
    )
    (net (code "172") (name "unconnected-(K4-Pad13)") (class "Default")
      (node (ref "K4") (pin "13") (pinfunction "13_13") (pintype "passive"))
    )
    (net (code "173") (name "unconnected-(K4-Pad15)") (class "Default")
      (node (ref "K4") (pin "15") (pinfunction "15_15") (pintype "passive"))
    )
    (net (code "174") (name "unconnected-(K4-Pad17)") (class "Default")
      (node (ref "K4") (pin "17") (pinfunction "17_17") (pintype "passive"))
    )
    (net (code "175") (name "unconnected-(K4-Pad18)") (class "Default")
      (node (ref "K4") (pin "18") (pinfunction "18_18") (pintype "passive"))
    )
    (net (code "176") (name "unconnected-(K4-Pad19)") (class "Default")
      (node (ref "K4") (pin "19") (pinfunction "19_19") (pintype "passive"))
    )
    (net (code "177") (name "unconnected-(K4-Pad20)") (class "Default")
      (node (ref "K4") (pin "20") (pinfunction "20_20") (pintype "passive"))
    )
    (net (code "178") (name "unconnected-(K4-Pad21)") (class "Default")
      (node (ref "K4") (pin "21") (pinfunction "21_21") (pintype "passive"))
    )
    (net (code "179") (name "unconnected-(K4-Pad23)") (class "Default")
      (node (ref "K4") (pin "23") (pinfunction "23_23") (pintype "passive"))
    )
    (net (code "180") (name "unconnected-(K4-Pad25)") (class "Default")
      (node (ref "K4") (pin "25") (pinfunction "25_25") (pintype "passive"))
    )
    (net (code "181") (name "unconnected-(K4-Pad27)") (class "Default")
      (node (ref "K4") (pin "27") (pinfunction "27_27") (pintype "passive"))
    )
    (net (code "182") (name "unconnected-(K4-Pad29)") (class "Default")
      (node (ref "K4") (pin "29") (pinfunction "29_29") (pintype "passive"))
    )
    (net (code "183") (name "unconnected-(K4-Pad31)") (class "Default")
      (node (ref "K4") (pin "31") (pinfunction "31_31") (pintype "passive"))
    )
    (net (code "184") (name "unconnected-(K4-Pad32)") (class "Default")
      (node (ref "K4") (pin "32") (pinfunction "32_32") (pintype "passive"))
    )
    (net (code "185") (name "unconnected-(U$1-NC-Pad5)") (class "Default")
      (node (ref "U$1") (pin "5") (pinfunction "NC_5") (pintype "no_connect"))
    )
    (net (code "186") (name "unconnected-(U$1-NC_2-Pad8)") (class "Default")
      (node (ref "U$1") (pin "8") (pinfunction "NC_2_8") (pintype "no_connect"))
    )
    (net (code "187") (name "unconnected-(U$1-NC_3-Pad1)") (class "Default")
      (node (ref "U$1") (pin "1") (pinfunction "NC_3_1") (pintype "no_connect"))
    )
    (net (code "188") (name "unconnected-(U$2-NC-Pad5)") (class "Default")
      (node (ref "U$2") (pin "5") (pinfunction "NC_5") (pintype "no_connect"))
    )
    (net (code "189") (name "unconnected-(U$2-NC_2-Pad8)") (class "Default")
      (node (ref "U$2") (pin "8") (pinfunction "NC_2_8") (pintype "no_connect"))
    )
    (net (code "190") (name "unconnected-(U$2-NC_3-Pad1)") (class "Default")
      (node (ref "U$2") (pin "1") (pinfunction "NC_3_1") (pintype "no_connect"))
    )
    (net (code "191") (name "unconnected-(U$3-NC-Pad5)") (class "Default")
      (node (ref "U$3") (pin "5") (pinfunction "NC_5") (pintype "no_connect"))
    )
    (net (code "192") (name "unconnected-(U$3-NC_2-Pad8)") (class "Default")
      (node (ref "U$3") (pin "8") (pinfunction "NC_2_8") (pintype "no_connect"))
    )
    (net (code "193") (name "unconnected-(U$3-NC_3-Pad1)") (class "Default")
      (node (ref "U$3") (pin "1") (pinfunction "NC_3_1") (pintype "no_connect"))
    )
    (net (code "194") (name "unconnected-(U$4-NC-Pad5)") (class "Default")
      (node (ref "U$4") (pin "5") (pinfunction "NC_5") (pintype "no_connect"))
    )
    (net (code "195") (name "unconnected-(U$4-NC_2-Pad8)") (class "Default")
      (node (ref "U$4") (pin "8") (pinfunction "NC_2_8") (pintype "no_connect"))
    )
    (net (code "196") (name "unconnected-(U$4-NC_3-Pad1)") (class "Default")
      (node (ref "U$4") (pin "1") (pinfunction "NC_3_1") (pintype "no_connect"))
    )
    (net (code "197") (name "unconnected-(U$5-NC-Pad5)") (class "Default")
      (node (ref "U$5") (pin "5") (pinfunction "NC_5") (pintype "no_connect"))
    )
    (net (code "198") (name "unconnected-(U$5-NC_2-Pad8)") (class "Default")
      (node (ref "U$5") (pin "8") (pinfunction "NC_2_8") (pintype "no_connect"))
    )
    (net (code "199") (name "unconnected-(U$5-NC_3-Pad1)") (class "Default")
      (node (ref "U$5") (pin "1") (pinfunction "NC_3_1") (pintype "no_connect"))
    )
    (net (code "200") (name "unconnected-(U$6-NC-Pad5)") (class "Default")
      (node (ref "U$6") (pin "5") (pinfunction "NC_5") (pintype "no_connect"))
    )
    (net (code "201") (name "unconnected-(U$6-NC_2-Pad8)") (class "Default")
      (node (ref "U$6") (pin "8") (pinfunction "NC_2_8") (pintype "no_connect"))
    )
    (net (code "202") (name "unconnected-(U$6-NC_3-Pad1)") (class "Default")
      (node (ref "U$6") (pin "1") (pinfunction "NC_3_1") (pintype "no_connect"))
    )
    (net (code "203") (name "unconnected-(U$7-NC-Pad5)") (class "Default")
      (node (ref "U$7") (pin "5") (pinfunction "NC_5") (pintype "no_connect"))
    )
    (net (code "204") (name "unconnected-(U$7-NC_2-Pad8)") (class "Default")
      (node (ref "U$7") (pin "8") (pinfunction "NC_2_8") (pintype "no_connect"))
    )
    (net (code "205") (name "unconnected-(U$7-NC_3-Pad1)") (class "Default")
      (node (ref "U$7") (pin "1") (pinfunction "NC_3_1") (pintype "no_connect"))
    )
    (net (code "206") (name "unconnected-(U$8-NC-Pad5)") (class "Default")
      (node (ref "U$8") (pin "5") (pinfunction "NC_5") (pintype "no_connect"))
    )
    (net (code "207") (name "unconnected-(U$8-NC_2-Pad8)") (class "Default")
      (node (ref "U$8") (pin "8") (pinfunction "NC_2_8") (pintype "no_connect"))
    )
    (net (code "208") (name "unconnected-(U$8-NC_3-Pad1)") (class "Default")
      (node (ref "U$8") (pin "1") (pinfunction "NC_3_1") (pintype "no_connect"))
    )
    (net (code "209") (name "unconnected-(U$9-NC-Pad5)") (class "Default")
      (node (ref "U$9") (pin "5") (pinfunction "NC_5") (pintype "no_connect"))
    )
    (net (code "210") (name "unconnected-(U$9-NC_2-Pad8)") (class "Default")
      (node (ref "U$9") (pin "8") (pinfunction "NC_2_8") (pintype "no_connect"))
    )
    (net (code "211") (name "unconnected-(U$9-NC_3-Pad1)") (class "Default")
      (node (ref "U$9") (pin "1") (pinfunction "NC_3_1") (pintype "no_connect"))
    )
    (net (code "212") (name "unconnected-(U$10-NC-Pad5)") (class "Default")
      (node (ref "U$10") (pin "5") (pinfunction "NC_5") (pintype "no_connect"))
    )
    (net (code "213") (name "unconnected-(U$10-NC_2-Pad8)") (class "Default")
      (node (ref "U$10") (pin "8") (pinfunction "NC_2_8") (pintype "no_connect"))
    )
    (net (code "214") (name "unconnected-(U$10-NC_3-Pad1)") (class "Default")
      (node (ref "U$10") (pin "1") (pinfunction "NC_3_1") (pintype "no_connect"))
    )
    (net (code "215") (name "unconnected-(U$11-NC-Pad5)") (class "Default")
      (node (ref "U$11") (pin "5") (pinfunction "NC_5") (pintype "no_connect"))
    )
    (net (code "216") (name "unconnected-(U$11-NC_2-Pad8)") (class "Default")
      (node (ref "U$11") (pin "8") (pinfunction "NC_2_8") (pintype "no_connect"))
    )
    (net (code "217") (name "unconnected-(U$11-NC_3-Pad1)") (class "Default")
      (node (ref "U$11") (pin "1") (pinfunction "NC_3_1") (pintype "no_connect"))
    )
    (net (code "218") (name "unconnected-(U$12-NC-Pad5)") (class "Default")
      (node (ref "U$12") (pin "5") (pinfunction "NC_5") (pintype "no_connect"))
    )
    (net (code "219") (name "unconnected-(U$12-NC_2-Pad8)") (class "Default")
      (node (ref "U$12") (pin "8") (pinfunction "NC_2_8") (pintype "no_connect"))
    )
    (net (code "220") (name "unconnected-(U$12-NC_3-Pad1)") (class "Default")
      (node (ref "U$12") (pin "1") (pinfunction "NC_3_1") (pintype "no_connect"))
    )
    (net (code "221") (name "unconnected-(U$13-NC-Pad5)") (class "Default")
      (node (ref "U$13") (pin "5") (pinfunction "NC_5") (pintype "no_connect"))
    )
    (net (code "222") (name "unconnected-(U$13-NC_2-Pad8)") (class "Default")
      (node (ref "U$13") (pin "8") (pinfunction "NC_2_8") (pintype "no_connect"))
    )
    (net (code "223") (name "unconnected-(U$13-NC_3-Pad1)") (class "Default")
      (node (ref "U$13") (pin "1") (pinfunction "NC_3_1") (pintype "no_connect"))
    )
    (net (code "224") (name "unconnected-(U$14-NC-Pad5)") (class "Default")
      (node (ref "U$14") (pin "5") (pinfunction "NC_5") (pintype "no_connect"))
    )
    (net (code "225") (name "unconnected-(U$14-NC_2-Pad8)") (class "Default")
      (node (ref "U$14") (pin "8") (pinfunction "NC_2_8") (pintype "no_connect"))
    )
    (net (code "226") (name "unconnected-(U$14-NC_3-Pad1)") (class "Default")
      (node (ref "U$14") (pin "1") (pinfunction "NC_3_1") (pintype "no_connect"))
    )
    (net (code "227") (name "unconnected-(U$15-NC-Pad5)") (class "Default")
      (node (ref "U$15") (pin "5") (pinfunction "NC_5") (pintype "no_connect"))
    )
    (net (code "228") (name "unconnected-(U$15-NC_2-Pad8)") (class "Default")
      (node (ref "U$15") (pin "8") (pinfunction "NC_2_8") (pintype "no_connect"))
    )
    (net (code "229") (name "unconnected-(U$15-NC_3-Pad1)") (class "Default")
      (node (ref "U$15") (pin "1") (pinfunction "NC_3_1") (pintype "no_connect"))
    )
    (net (code "230") (name "unconnected-(U$16-NC-Pad5)") (class "Default")
      (node (ref "U$16") (pin "5") (pinfunction "NC_5") (pintype "no_connect"))
    )
    (net (code "231") (name "unconnected-(U$16-NC_2-Pad8)") (class "Default")
      (node (ref "U$16") (pin "8") (pinfunction "NC_2_8") (pintype "no_connect"))
    )
    (net (code "232") (name "unconnected-(U$16-NC_3-Pad1)") (class "Default")
      (node (ref "U$16") (pin "1") (pinfunction "NC_3_1") (pintype "no_connect"))
    )
    (net (code "233") (name "unconnected-(U1-NC-Pad14)") (class "Default")
      (node (ref "U1") (pin "14") (pinfunction "NC_14") (pintype "no_connect"))
    )
    (net (code "234") (name "unconnected-(U1-NC_2-Pad13)") (class "Default")
      (node (ref "U1") (pin "13") (pinfunction "NC_2_13") (pintype "no_connect"))
    )
  )
)
